# NixieClock.net
KiCad netlist of a schematic drawn in EAGLE
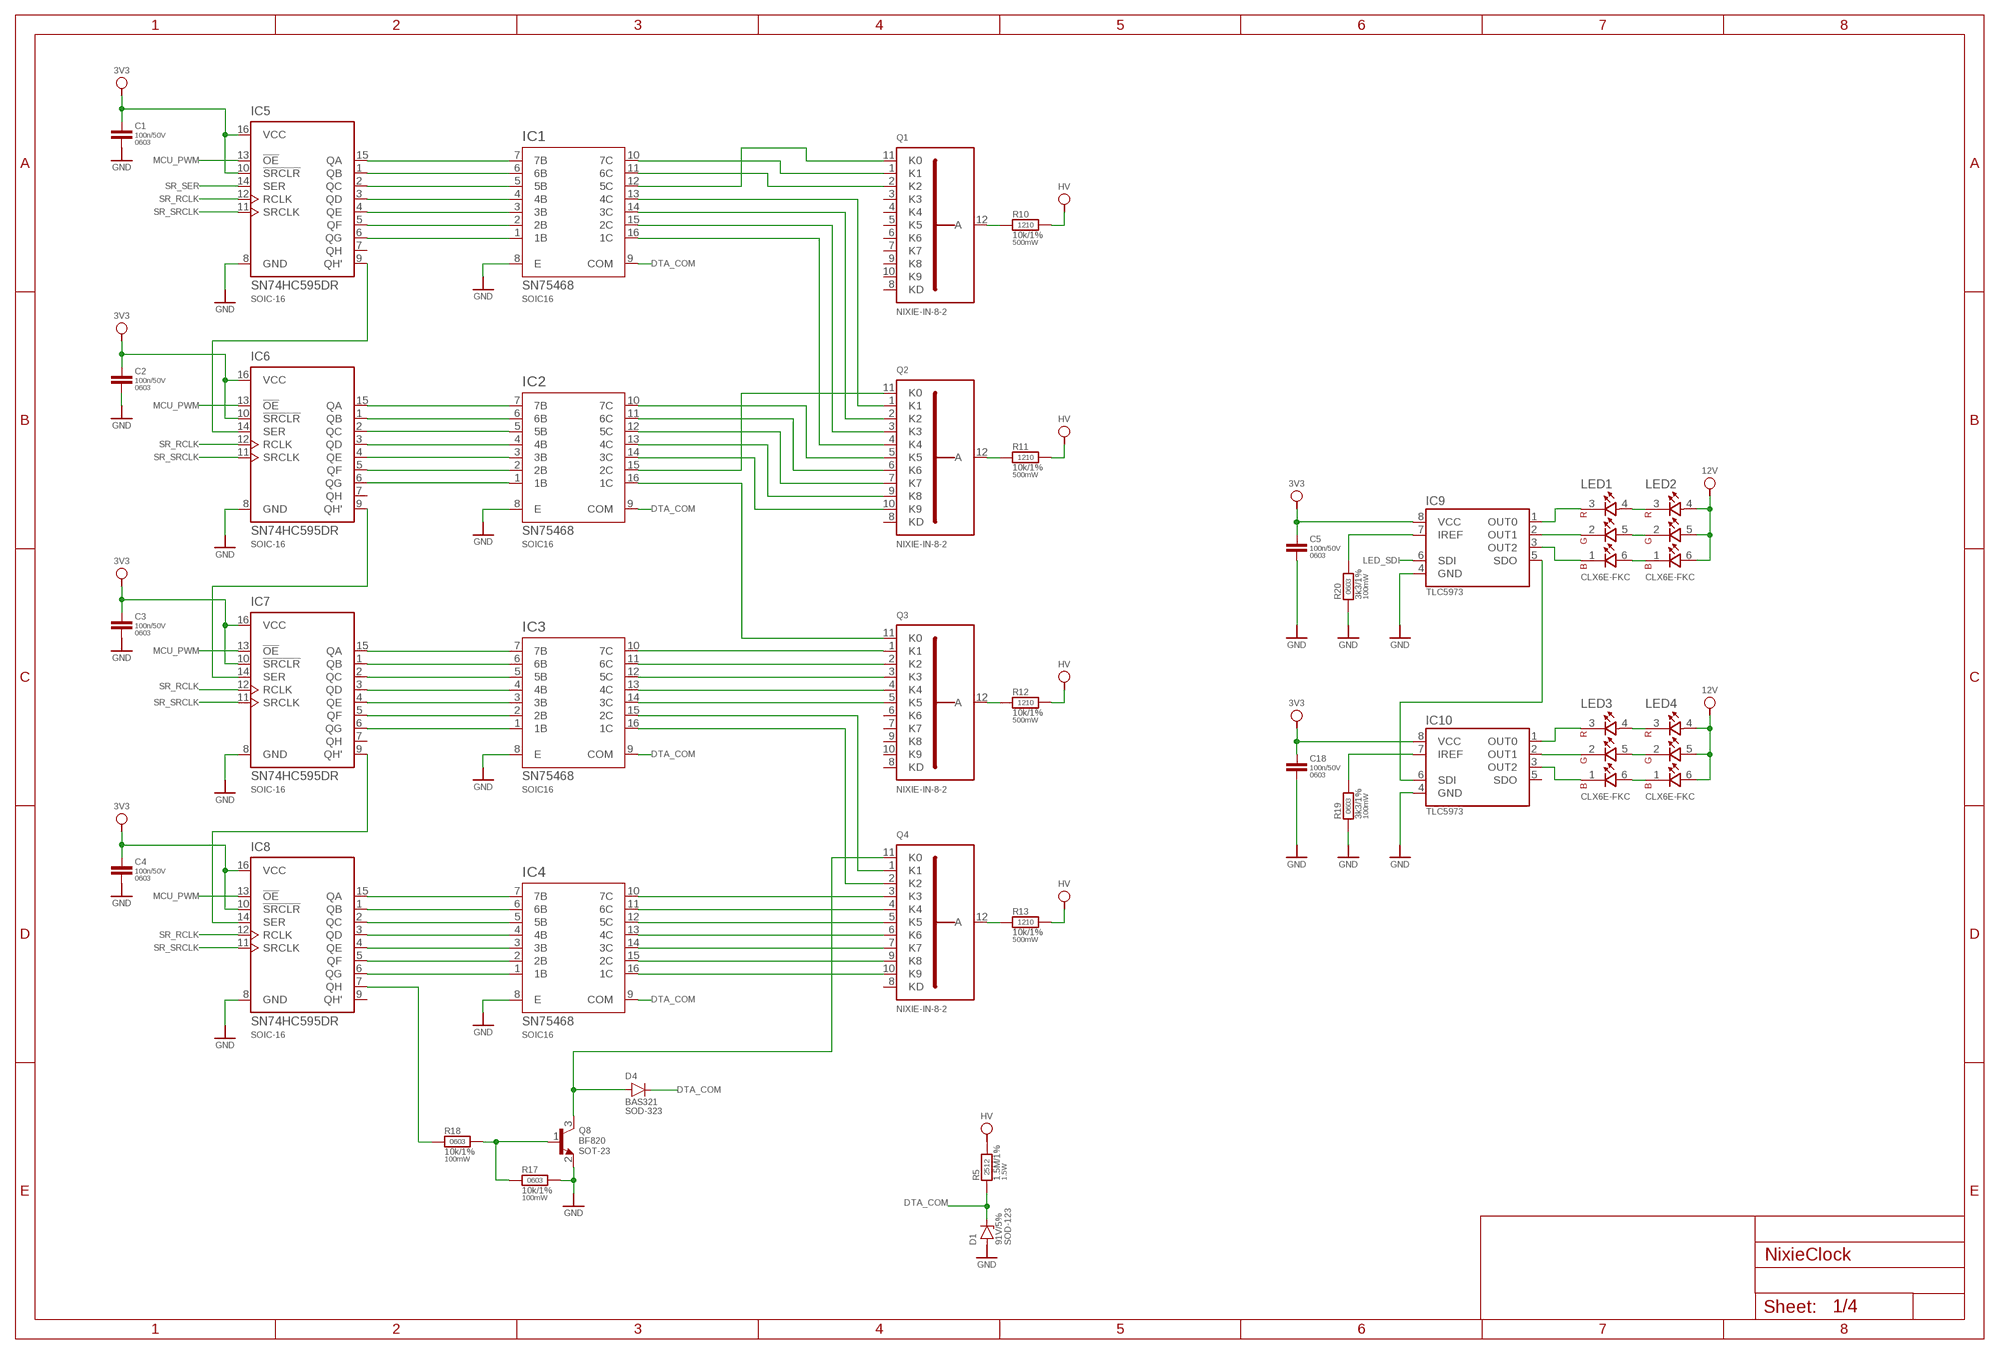
[diagram p0: schematic, sheet 1]
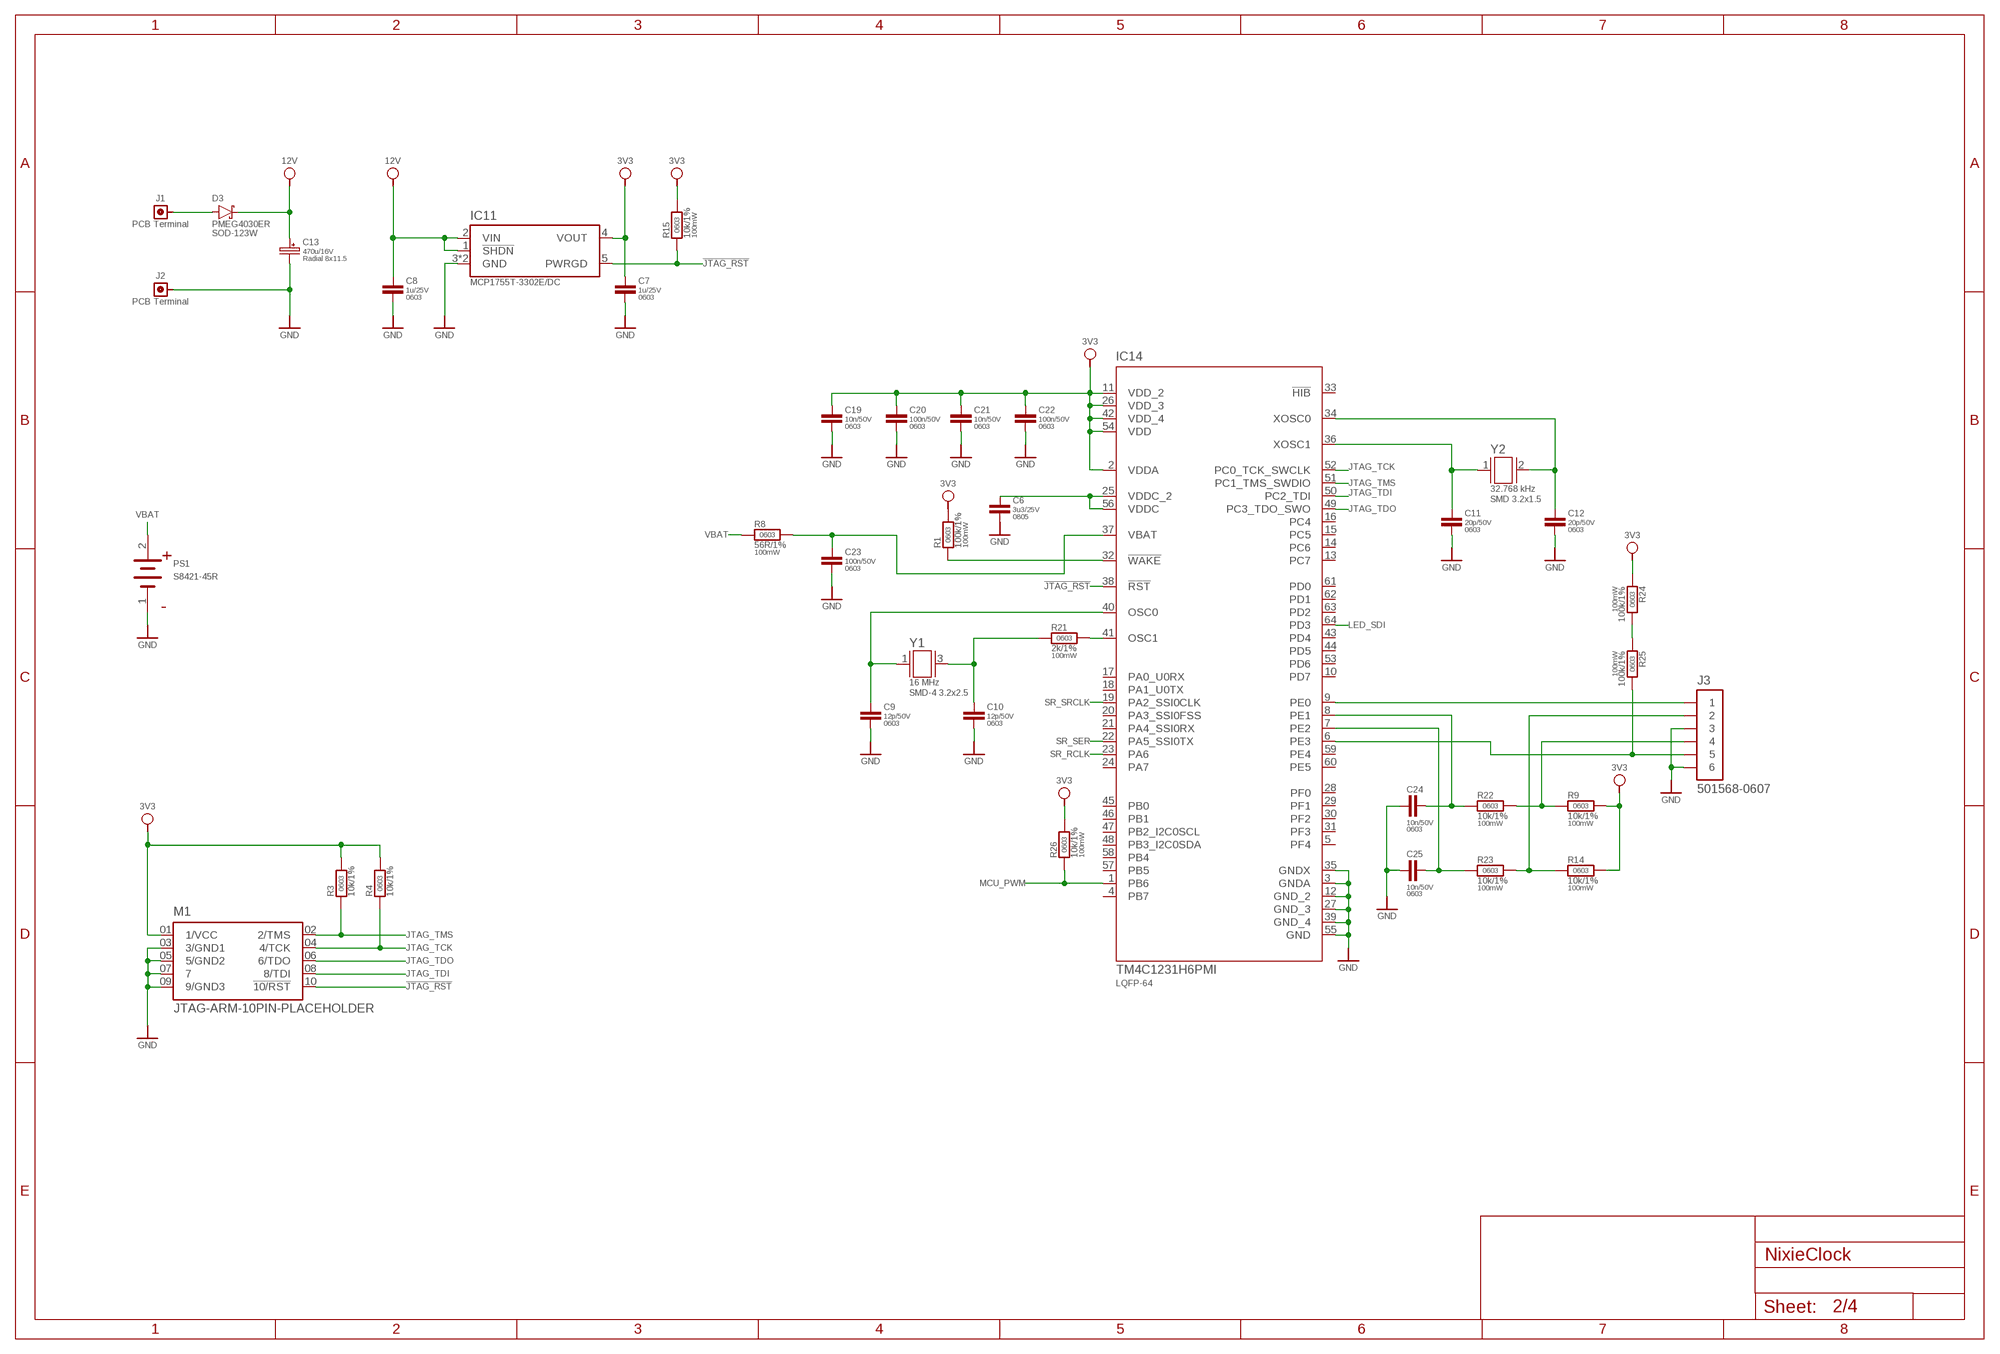
[diagram p1: schematic, sheet 2]
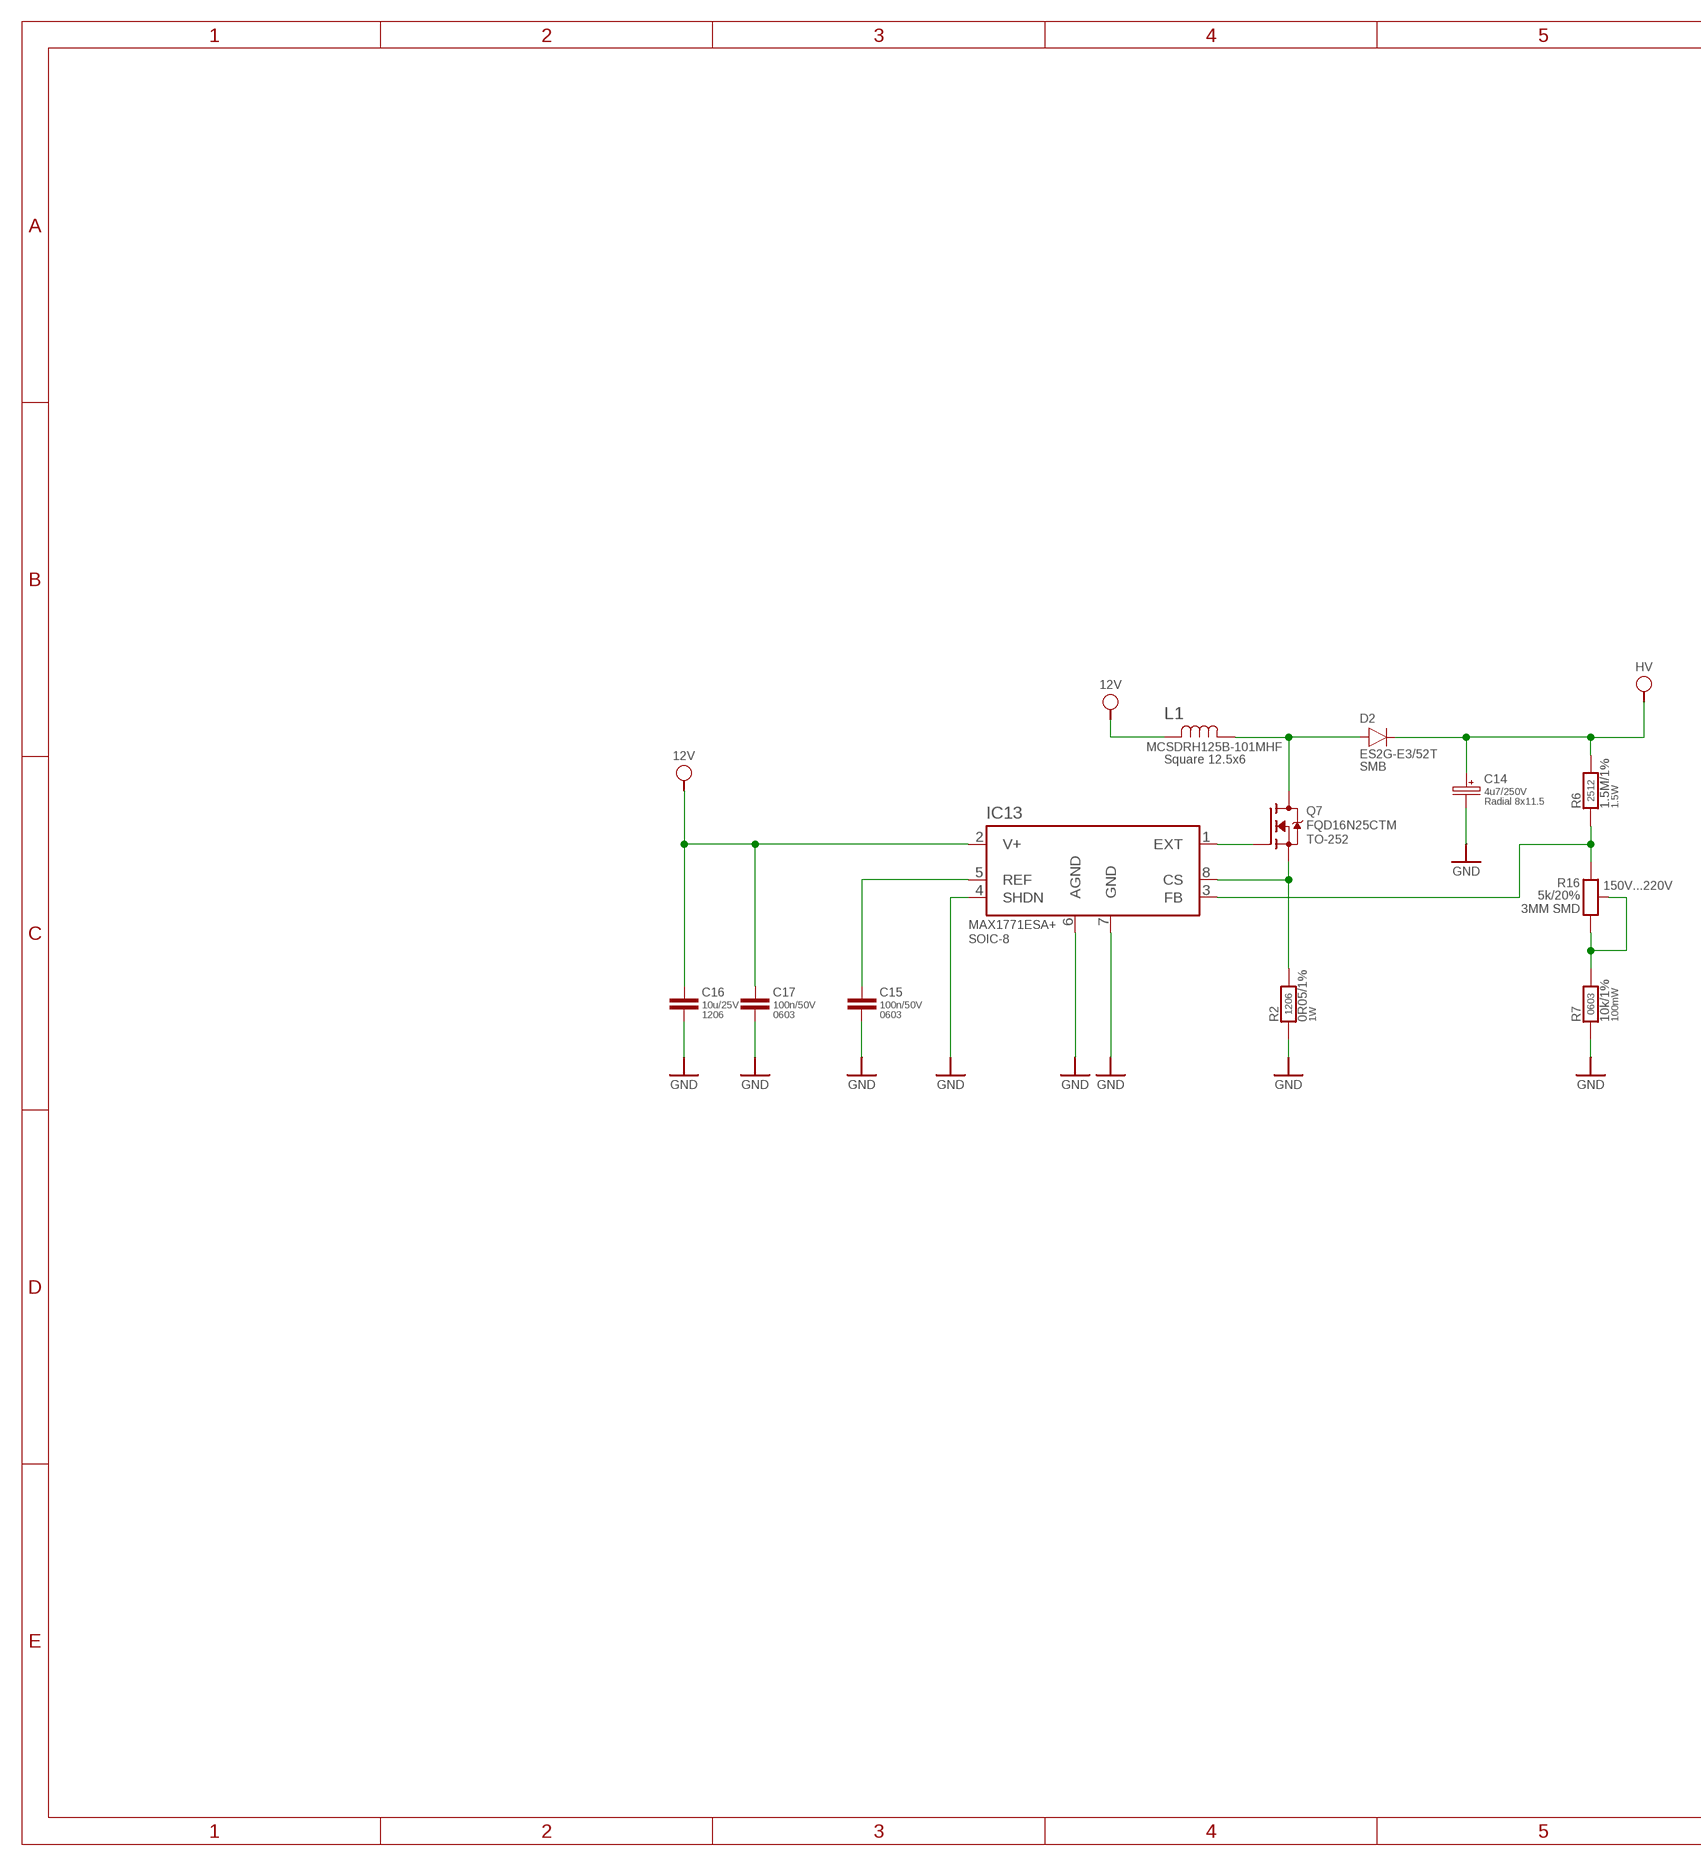
[diagram p2: schematic, sheet 3, part 1 of 2]
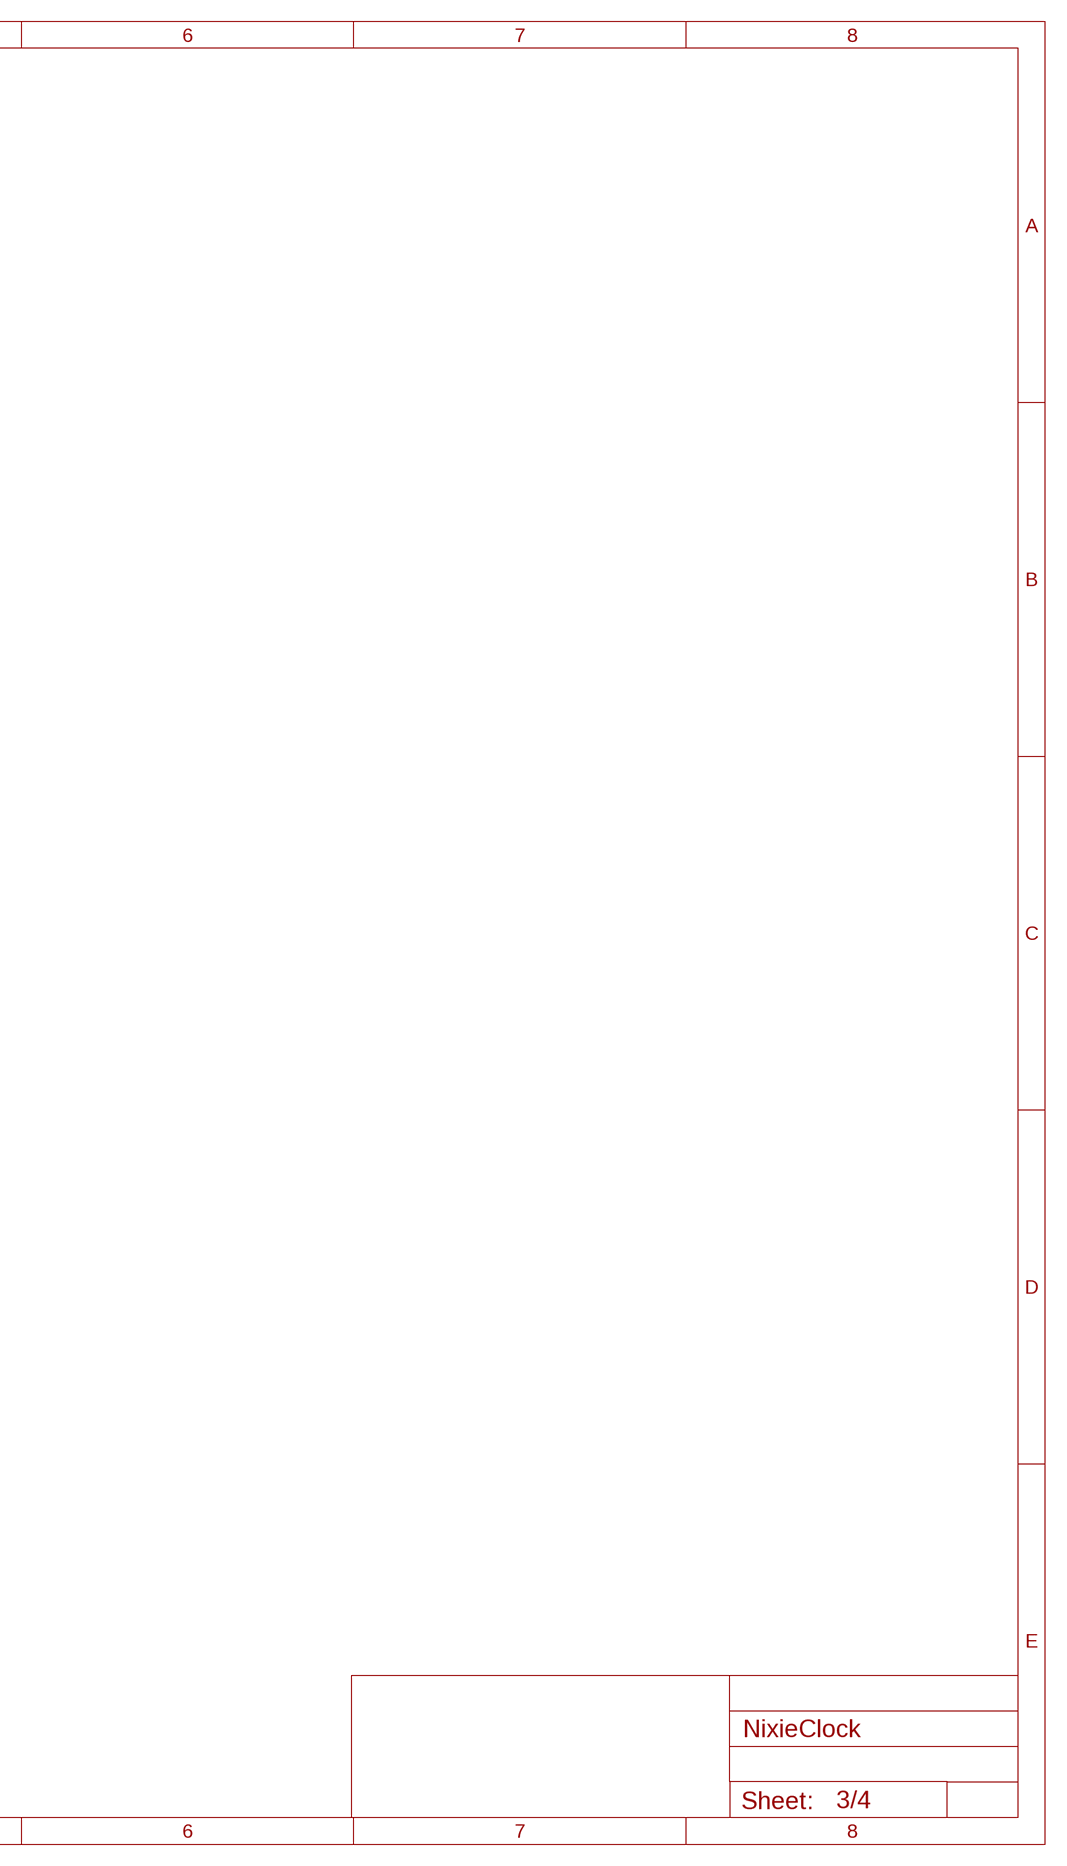
[diagram p3: schematic, sheet 3, part 2 of 2]
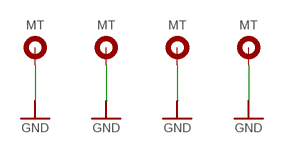
[diagram p4: schematic, sheet 4]

(export (version "E")
  (design (tool "Eeschema 10.0.6"))
  (components
    (comp (ref "MT1")
      (value "MOUNTING_HOLE_3MM")
      (footprint "eagle-import:MOUNTING_HOLE_3MM")
      (libsource (lib "eagle-import") (part "MOUNTING_HOLE_3MM"))
    )
    (comp (ref "MT2")
      (value "MOUNTING_HOLE_3MM")
      (footprint "eagle-import:MOUNTING_HOLE_3MM")
      (libsource (lib "eagle-import") (part "MOUNTING_HOLE_3MM"))
    )
    (comp (ref "MT3")
      (value "MOUNTING_HOLE_3MM")
      (footprint "eagle-import:MOUNTING_HOLE_3MM")
      (libsource (lib "eagle-import") (part "MOUNTING_HOLE_3MM"))
    )
    (comp (ref "MT4")
      (value "MOUNTING_HOLE_3MM")
      (footprint "eagle-import:MOUNTING_HOLE_3MM")
      (libsource (lib "eagle-import") (part "MOUNTING_HOLE_3MM"))
    )
    (comp (ref "C14")
      (value "4u7/250V")
      (footprint "eagle-import:CAPPRD350W60D800H1150B")
      (fields
        (field (name "PACKAGE") "Radial 8x11.5")
        (field (name "MANUFACTURER") "Panasonic")
        (field (name "PARTNUMBER") "ECA2EHG4R7")
      )
      (libsource (lib "eagle-import") (part "ECA2EHG4R7"))
    )
    (comp (ref "C15")
      (value "100n/50V")
      (footprint "eagle-import:CAPC1608X80N")
      (fields
        (field (name "PACKAGE") "0603")
        (field (name "MANUFACTURER") "KEMET")
        (field (name "PARTNUMBER") "C0603C104M5RACTU")
      )
      (libsource (lib "eagle-import") (part "C0603C104M5RACTU"))
    )
    (comp (ref "C16")
      (value "10u/25V")
      (footprint "eagle-import:CAPC3216X170N")
      (fields
        (field (name "PACKAGE") "1206")
        (field (name "MANUFACTURER") "KEMET")
        (field (name "PARTNUMBER") "C1206C106K3PACTU")
      )
      (libsource (lib "eagle-import") (part "C1206C106K3PACTU"))
    )
    (comp (ref "C17")
      (value "100n/50V")
      (footprint "eagle-import:CAPC1608X80N")
      (fields
        (field (name "PACKAGE") "0603")
        (field (name "MANUFACTURER") "KEMET")
        (field (name "PARTNUMBER") "C0603C104M5RACTU")
      )
      (libsource (lib "eagle-import") (part "C0603C104M5RACTU"))
    )
    (comp (ref "D2")
      (value "ES2G-E3/52T")
      (footprint "eagle-import:DIOM5436X245N")
      (fields (field (name "PACKAGE") "SMB") (field (name "MANUFACTURER") "VISHAY"))
      (libsource (lib "eagle-import") (part "ES2G-E3/52T"))
    )
    (comp (ref "IC13")
      (value "MAX1771ESA+")
      (footprint "eagle-import:SOIC127P600X175-8N")
      (fields (field (name "PACKAGE") "SOIC-8") (field (name "MANUFACTURER") "Maxim Integrated"))
      (libsource (lib "eagle-import") (part "MAX1771ESA+"))
    )
    (comp (ref "L1")
      (value "MCSDRH125B-101MHF")
      (footprint "eagle-import:INDM120120X600N")
      (fields (field (name "PACKAGE") "Square 12.5x6") (field (name "MANUFACTURER") "Multicomp PRO"))
      (libsource (lib "eagle-import") (part "MCSDRH125B-101MHF"))
    )
    (comp (ref "Q7")
      (value "FQD16N25CTM")
      (footprint "eagle-import:TO230P990X240-3N")
      (fields (field (name "PACKAGE") "TO-252") (field (name "MANUFACTURER") "ON Semiconductor"))
      (libsource (lib "eagle-import") (part "FQD16N25CTM"))
    )
    (comp (ref "R2")
      (value "0R05/1%")
      (footprint "eagle-import:RESC3216X70N")
      (fields
        (field (name "PARAMETER") "1W")
        (field (name "PACKAGE") "1206")
        (field (name "MANUFACTURER") "Panasonic")
        (field (name "PARTNUMBER") "ERJ8CWFR050V")
      )
      (libsource (lib "eagle-import") (part "ERJ8CWFR050V"))
    )
    (comp (ref "R6")
      (value "1.5M/1%")
      (footprint "eagle-import:RESC6331X65N")
      (fields
        (field (name "PARAMETER") "1.5W")
        (field (name "PACKAGE") "2512")
        (field (name "MANUFACTURER") "MULTICOMP PRO")
        (field (name "PARTNUMBER") "MCPWR12FTEA1504")
      )
      (libsource (lib "eagle-import") (part "MCPWR12FTEA1504"))
    )
    (comp (ref "R7")
      (value "10k/1%")
      (footprint "eagle-import:RESC1608X50N")
      (fields
        (field (name "PARAMETER") "100mW")
        (field (name "PACKAGE") "0603")
        (field (name "MANUFACTURER") "VISHAY")
        (field (name "PARTNUMBER") "CRCW060310K0FKEA")
      )
      (libsource (lib "eagle-import") (part "CRCW060310K0FKEA"))
    )
    (comp (ref "R16")
      (value "5k/20%")
      (footprint "eagle-import:22A")
      (fields (field (name "PACKAGE") "3MM SMD") (field (name "MANUFACTURER") "TT ELECTRONICS / BI TECHNOL"))
      (libsource (lib "eagle-import") (part "22AR5K"))
    )
    (comp (ref "C1")
      (value "100n/50V")
      (footprint "eagle-import:CAPC1608X80N")
      (fields
        (field (name "PACKAGE") "0603")
        (field (name "MANUFACTURER") "KEMET")
        (field (name "PARTNUMBER") "C0603C104M5RACTU")
      )
      (libsource (lib "eagle-import") (part "C0603C104M5RACTU"))
    )
    (comp (ref "C2")
      (value "100n/50V")
      (footprint "eagle-import:CAPC1608X80N")
      (fields
        (field (name "PACKAGE") "0603")
        (field (name "MANUFACTURER") "KEMET")
        (field (name "PARTNUMBER") "C0603C104M5RACTU")
      )
      (libsource (lib "eagle-import") (part "C0603C104M5RACTU"))
    )
    (comp (ref "C3")
      (value "100n/50V")
      (footprint "eagle-import:CAPC1608X80N")
      (fields
        (field (name "PACKAGE") "0603")
        (field (name "MANUFACTURER") "KEMET")
        (field (name "PARTNUMBER") "C0603C104M5RACTU")
      )
      (libsource (lib "eagle-import") (part "C0603C104M5RACTU"))
    )
    (comp (ref "C4")
      (value "100n/50V")
      (footprint "eagle-import:CAPC1608X80N")
      (fields
        (field (name "PACKAGE") "0603")
        (field (name "MANUFACTURER") "KEMET")
        (field (name "PARTNUMBER") "C0603C104M5RACTU")
      )
      (libsource (lib "eagle-import") (part "C0603C104M5RACTU"))
    )
    (comp (ref "C5")
      (value "100n/50V")
      (footprint "eagle-import:CAPC1608X80N")
      (fields
        (field (name "PACKAGE") "0603")
        (field (name "MANUFACTURER") "KEMET")
        (field (name "PARTNUMBER") "C0603C104M5RACTU")
      )
      (libsource (lib "eagle-import") (part "C0603C104M5RACTU"))
    )
    (comp (ref "C18")
      (value "100n/50V")
      (footprint "eagle-import:CAPC1608X80N")
      (fields
        (field (name "PACKAGE") "0603")
        (field (name "MANUFACTURER") "KEMET")
        (field (name "PARTNUMBER") "C0603C104M5RACTU")
      )
      (libsource (lib "eagle-import") (part "C0603C104M5RACTU"))
    )
    (comp (ref "D1")
      (value "91V/5%")
      (footprint "eagle-import:SOD3716X135N")
      (fields
        (field (name "PACKAGE") "SOD-123")
        (field (name "MANUFACTURER") "ON Semiconductor")
        (field (name "PARTNUMBER") "MMSZ5270BT1G")
      )
      (libsource (lib "eagle-import") (part "MMSZ5270BT1G"))
    )
    (comp (ref "D4")
      (value "BAS321")
      (footprint "eagle-import:SOD2512X110N")
      (fields
        (field (name "PACKAGE") "SOD-323")
        (field (name "MANUFACTURER") "NEXPERIA")
        (field (name "PARTNUMBER") "BAS321/8F")
      )
      (libsource (lib "eagle-import") (part "BAS321"))
    )
    (comp (ref "IC1")
      (value "SN75468")
      (footprint "eagle-import:SOIC127P600X175-16N")
      (fields
        (field (name "PACKAGE") "SOIC16")
        (field (name "MANUFACTURER") "Texas Instruments")
        (field (name "PARTNUMBER") "SN75468D")
      )
      (libsource (lib "eagle-import") (part "SN75468"))
    )
    (comp (ref "IC2")
      (value "SN75468")
      (footprint "eagle-import:SOIC127P600X175-16N")
      (fields
        (field (name "PACKAGE") "SOIC16")
        (field (name "MANUFACTURER") "Texas Instruments")
        (field (name "PARTNUMBER") "SN75468D")
      )
      (libsource (lib "eagle-import") (part "SN75468"))
    )
    (comp (ref "IC3")
      (value "SN75468")
      (footprint "eagle-import:SOIC127P600X175-16N")
      (fields
        (field (name "PACKAGE") "SOIC16")
        (field (name "MANUFACTURER") "Texas Instruments")
        (field (name "PARTNUMBER") "SN75468D")
      )
      (libsource (lib "eagle-import") (part "SN75468"))
    )
    (comp (ref "IC4")
      (value "SN75468")
      (footprint "eagle-import:SOIC127P600X175-16N")
      (fields
        (field (name "PACKAGE") "SOIC16")
        (field (name "MANUFACTURER") "Texas Instruments")
        (field (name "PARTNUMBER") "SN75468D")
      )
      (libsource (lib "eagle-import") (part "SN75468"))
    )
    (comp (ref "IC5")
      (value "SN74HC595DR")
      (footprint "eagle-import:SOIC127P600X175-16N")
      (fields (field (name "PACKAGE") "SOIC-16") (field (name "MANUFACTURER") "Texas Instruments"))
      (libsource (lib "eagle-import") (part "SN74HC595DR"))
    )
    (comp (ref "IC6")
      (value "SN74HC595DR")
      (footprint "eagle-import:SOIC127P600X175-16N")
      (fields (field (name "PACKAGE") "SOIC-16") (field (name "MANUFACTURER") "Texas Instruments"))
      (libsource (lib "eagle-import") (part "SN74HC595DR"))
    )
    (comp (ref "IC7")
      (value "SN74HC595DR")
      (footprint "eagle-import:SOIC127P600X175-16N")
      (fields (field (name "PACKAGE") "SOIC-16") (field (name "MANUFACTURER") "Texas Instruments"))
      (libsource (lib "eagle-import") (part "SN74HC595DR"))
    )
    (comp (ref "IC8")
      (value "SN74HC595DR")
      (footprint "eagle-import:SOIC127P600X175-16N")
      (fields (field (name "PACKAGE") "SOIC-16") (field (name "MANUFACTURER") "Texas Instruments"))
      (libsource (lib "eagle-import") (part "SN74HC595DR"))
    )
    (comp (ref "IC9")
      (value "TLC5973")
      (footprint "eagle-import:SOIC127P600X175-8N")
      (fields (field (name "MANUFACTURER") "Texas Instruments"))
      (libsource (lib "eagle-import") (part "TLC5973"))
    )
    (comp (ref "IC10")
      (value "TLC5973")
      (footprint "eagle-import:SOIC127P600X175-8N")
      (fields (field (name "MANUFACTURER") "Texas Instruments"))
      (libsource (lib "eagle-import") (part "TLC5973"))
    )
    (comp (ref "LED1")
      (value "CLX6E-FKC")
      (footprint "eagle-import:CLX6E-FKC")
      (fields (field (name "MANUFACTURER") "CREE") (field (name "PARTNUMBER") "CLX6E-FKC-CH1M1D1BB7C3D3"))
      (libsource (lib "eagle-import") (part "CLX6E-FKC"))
    )
    (comp (ref "LED2")
      (value "CLX6E-FKC")
      (footprint "eagle-import:CLX6E-FKC")
      (fields (field (name "MANUFACTURER") "CREE") (field (name "PARTNUMBER") "CLX6E-FKC-CH1M1D1BB7C3D3"))
      (libsource (lib "eagle-import") (part "CLX6E-FKC"))
    )
    (comp (ref "LED3")
      (value "CLX6E-FKC")
      (footprint "eagle-import:CLX6E-FKC")
      (fields (field (name "MANUFACTURER") "CREE") (field (name "PARTNUMBER") "CLX6E-FKC-CH1M1D1BB7C3D3"))
      (libsource (lib "eagle-import") (part "CLX6E-FKC"))
    )
    (comp (ref "LED4")
      (value "CLX6E-FKC")
      (footprint "eagle-import:CLX6E-FKC")
      (fields (field (name "MANUFACTURER") "CREE") (field (name "PARTNUMBER") "CLX6E-FKC-CH1M1D1BB7C3D3"))
      (libsource (lib "eagle-import") (part "CLX6E-FKC"))
    )
    (comp (ref "Q1")
      (value "NIXIE-IN-8-2")
      (footprint "eagle-import:NIXIE-IN-8-2")
      (libsource (lib "eagle-import") (part "NIXIE-IN-8-2"))
    )
    (comp (ref "Q2")
      (value "NIXIE-IN-8-2")
      (footprint "eagle-import:NIXIE-IN-8-2")
      (libsource (lib "eagle-import") (part "NIXIE-IN-8-2"))
    )
    (comp (ref "Q3")
      (value "NIXIE-IN-8-2")
      (footprint "eagle-import:NIXIE-IN-8-2")
      (libsource (lib "eagle-import") (part "NIXIE-IN-8-2"))
    )
    (comp (ref "Q4")
      (value "NIXIE-IN-8-2")
      (footprint "eagle-import:NIXIE-IN-8-2")
      (libsource (lib "eagle-import") (part "NIXIE-IN-8-2"))
    )
    (comp (ref "Q8")
      (value "BF820")
      (footprint "eagle-import:SOT95P230X110-3N")
      (fields (field (name "PACKAGE") "SOT-23") (field (name "MANUFACTURER") "NEXPERIA"))
      (libsource (lib "eagle-import") (part "BF820"))
    )
    (comp (ref "R5")
      (value "1.5M/1%")
      (footprint "eagle-import:RESC6331X65N")
      (fields
        (field (name "PARAMETER") "1.5W")
        (field (name "PACKAGE") "2512")
        (field (name "MANUFACTURER") "MULTICOMP PRO")
        (field (name "PARTNUMBER") "MCPWR12FTEA1504")
      )
      (libsource (lib "eagle-import") (part "MCPWR12FTEA1504"))
    )
    (comp (ref "R10")
      (value "10k/1%")
      (footprint "eagle-import:RESC3225X60N")
      (fields
        (field (name "PARAMETER") "500mW")
        (field (name "PACKAGE") "1210")
        (field (name "MANUFACTURER") "VISHAY")
        (field (name "PARTNUMBER") "CRCW121010K0FKEA")
      )
      (libsource (lib "eagle-import") (part "CRCW121010K0FKEA"))
    )
    (comp (ref "R11")
      (value "10k/1%")
      (footprint "eagle-import:RESC3225X60N")
      (fields
        (field (name "PARAMETER") "500mW")
        (field (name "PACKAGE") "1210")
        (field (name "MANUFACTURER") "VISHAY")
        (field (name "PARTNUMBER") "CRCW121010K0FKEA")
      )
      (libsource (lib "eagle-import") (part "CRCW121010K0FKEA"))
    )
    (comp (ref "R12")
      (value "10k/1%")
      (footprint "eagle-import:RESC3225X60N")
      (fields
        (field (name "PARAMETER") "500mW")
        (field (name "PACKAGE") "1210")
        (field (name "MANUFACTURER") "VISHAY")
        (field (name "PARTNUMBER") "CRCW121010K0FKEA")
      )
      (libsource (lib "eagle-import") (part "CRCW121010K0FKEA"))
    )
    (comp (ref "R13")
      (value "10k/1%")
      (footprint "eagle-import:RESC3225X60N")
      (fields
        (field (name "PARAMETER") "500mW")
        (field (name "PACKAGE") "1210")
        (field (name "MANUFACTURER") "VISHAY")
        (field (name "PARTNUMBER") "CRCW121010K0FKEA")
      )
      (libsource (lib "eagle-import") (part "CRCW121010K0FKEA"))
    )
    (comp (ref "R17")
      (value "10k/1%")
      (footprint "eagle-import:RESC1608X50N")
      (fields
        (field (name "PARAMETER") "100mW")
        (field (name "PACKAGE") "0603")
        (field (name "MANUFACTURER") "VISHAY")
        (field (name "PARTNUMBER") "CRCW060310K0FKEA")
      )
      (libsource (lib "eagle-import") (part "CRCW060310K0FKEA"))
    )
    (comp (ref "R18")
      (value "10k/1%")
      (footprint "eagle-import:RESC1608X50N")
      (fields
        (field (name "PARAMETER") "100mW")
        (field (name "PACKAGE") "0603")
        (field (name "MANUFACTURER") "VISHAY")
        (field (name "PARTNUMBER") "CRCW060310K0FKEA")
      )
      (libsource (lib "eagle-import") (part "CRCW060310K0FKEA"))
    )
    (comp (ref "R19")
      (value "3k3/1%")
      (footprint "eagle-import:RESC1608X50N")
      (fields
        (field (name "PARAMETER") "100mW")
        (field (name "PACKAGE") "0603")
        (field (name "MANUFACTURER") "MULTICOMP PRO")
        (field (name "PARTNUMBER") "MCWR06X3301FTL")
      )
      (libsource (lib "eagle-import") (part "MCWR06X3301FTL"))
    )
    (comp (ref "R20")
      (value "3k3/1%")
      (footprint "eagle-import:RESC1608X50N")
      (fields
        (field (name "PARAMETER") "100mW")
        (field (name "PACKAGE") "0603")
        (field (name "MANUFACTURER") "MULTICOMP PRO")
        (field (name "PARTNUMBER") "MCWR06X3301FTL")
      )
      (libsource (lib "eagle-import") (part "MCWR06X3301FTL"))
    )
    (comp (ref "C6")
      (value "3u3/25V")
      (footprint "eagle-import:CAPC2012X145N")
      (fields
        (field (name "PACKAGE") "0805")
        (field (name "MANUFACTURER") "TDK")
        (field (name "PARTNUMBER") "C2012X7R1E335K125AB")
      )
      (libsource (lib "eagle-import") (part "C2012X7R1E335K125"))
    )
    (comp (ref "C7")
      (value "1u/25V")
      (footprint "eagle-import:CAPC1608X80N")
      (fields
        (field (name "PACKAGE") "0603")
        (field (name "MANUFACTURER") "SAMSUNG ELECTRO-MECHANICS")
        (field (name "PARTNUMBER") "CL10A105KA8NNNC")
      )
      (libsource (lib "eagle-import") (part "CL10A105KA8NNNC"))
    )
    (comp (ref "C8")
      (value "1u/25V")
      (footprint "eagle-import:CAPC1608X80N")
      (fields
        (field (name "PACKAGE") "0603")
        (field (name "MANUFACTURER") "SAMSUNG ELECTRO-MECHANICS")
        (field (name "PARTNUMBER") "CL10A105KA8NNNC")
      )
      (libsource (lib "eagle-import") (part "CL10A105KA8NNNC"))
    )
    (comp (ref "C9")
      (value "12p/50V")
      (footprint "eagle-import:CAPC1608X80N")
      (fields
        (field (name "PACKAGE") "0603")
        (field (name "MANUFACTURER") "KEMET")
        (field (name "PARTNUMBER") "C0603C120J5GACTU")
      )
      (libsource (lib "eagle-import") (part "C0603C120J5GACTU"))
    )
    (comp (ref "C10")
      (value "12p/50V")
      (footprint "eagle-import:CAPC1608X80N")
      (fields
        (field (name "PACKAGE") "0603")
        (field (name "MANUFACTURER") "KEMET")
        (field (name "PARTNUMBER") "C0603C120J5GACTU")
      )
      (libsource (lib "eagle-import") (part "C0603C120J5GACTU"))
    )
    (comp (ref "C11")
      (value "20p/50V")
      (footprint "eagle-import:CAPC1608X80N")
      (fields
        (field (name "PACKAGE") "0603")
        (field (name "MANUFACTURER") "KEMET")
        (field (name "PARTNUMBER") "C0603C200J1GACTU")
      )
      (libsource (lib "eagle-import") (part "C0603C200J1GACTU"))
    )
    (comp (ref "C12")
      (value "20p/50V")
      (footprint "eagle-import:CAPC1608X80N")
      (fields
        (field (name "PACKAGE") "0603")
        (field (name "MANUFACTURER") "KEMET")
        (field (name "PARTNUMBER") "C0603C200J1GACTU")
      )
      (libsource (lib "eagle-import") (part "C0603C200J1GACTU"))
    )
    (comp (ref "C13")
      (value "470u/16V")
      (footprint "eagle-import:CAPPRD350W60D800H1150B")
      (fields
        (field (name "PACKAGE") "Radial 8x11.5")
        (field (name "MANUFACTURER") "Panasonic")
        (field (name "PARTNUMBER") "ECA1CM471")
      )
      (libsource (lib "eagle-import") (part "ECA1CM471"))
    )
    (comp (ref "C19")
      (value "10n/50V")
      (footprint "eagle-import:CAPC1608X80N")
      (fields
        (field (name "PACKAGE") "0603")
        (field (name "MANUFACTURER") "KEMET")
        (field (name "PARTNUMBER") "C0603C103K5RACTU")
      )
      (libsource (lib "eagle-import") (part "C0603C103K5RACTU"))
    )
    (comp (ref "C20")
      (value "100n/50V")
      (footprint "eagle-import:CAPC1608X80N")
      (fields
        (field (name "PACKAGE") "0603")
        (field (name "MANUFACTURER") "KEMET")
        (field (name "PARTNUMBER") "C0603C104M5RACTU")
      )
      (libsource (lib "eagle-import") (part "C0603C104M5RACTU"))
    )
    (comp (ref "C21")
      (value "10n/50V")
      (footprint "eagle-import:CAPC1608X80N")
      (fields
        (field (name "PACKAGE") "0603")
        (field (name "MANUFACTURER") "KEMET")
        (field (name "PARTNUMBER") "C0603C103K5RACTU")
      )
      (libsource (lib "eagle-import") (part "C0603C103K5RACTU"))
    )
    (comp (ref "C22")
      (value "100n/50V")
      (footprint "eagle-import:CAPC1608X80N")
      (fields
        (field (name "PACKAGE") "0603")
        (field (name "MANUFACTURER") "KEMET")
        (field (name "PARTNUMBER") "C0603C104M5RACTU")
      )
      (libsource (lib "eagle-import") (part "C0603C104M5RACTU"))
    )
    (comp (ref "C23")
      (value "100n/50V")
      (footprint "eagle-import:CAPC1608X80N")
      (fields
        (field (name "PACKAGE") "0603")
        (field (name "MANUFACTURER") "KEMET")
        (field (name "PARTNUMBER") "C0603C104M5RACTU")
      )
      (libsource (lib "eagle-import") (part "C0603C104M5RACTU"))
    )
    (comp (ref "C24")
      (value "10n/50V")
      (footprint "eagle-import:CAPC1608X80N")
      (fields
        (field (name "PACKAGE") "0603")
        (field (name "MANUFACTURER") "KEMET")
        (field (name "PARTNUMBER") "C0603C103K5RACTU")
      )
      (libsource (lib "eagle-import") (part "C0603C103K5RACTU"))
    )
    (comp (ref "C25")
      (value "10n/50V")
      (footprint "eagle-import:CAPC1608X80N")
      (fields
        (field (name "PACKAGE") "0603")
        (field (name "MANUFACTURER") "KEMET")
        (field (name "PARTNUMBER") "C0603C103K5RACTU")
      )
      (libsource (lib "eagle-import") (part "C0603C103K5RACTU"))
    )
    (comp (ref "D3")
      (value "PMEG4030ER")
      (footprint "eagle-import:SODFL3517X110N")
      (fields
        (field (name "PACKAGE") "SOD-123W")
        (field (name "MANUFACTURER") "NEXPERIA")
        (field (name "PARTNUMBER") "PMEG4030ER,115")
      )
      (libsource (lib "eagle-import") (part "PMEG4010CEJ"))
    )
    (comp (ref "IC11")
      (value "MCP1755T-3302E/DC")
      (footprint "eagle-import:SOT127P700X180-6N")
      (fields (field (name "MANUFACTURER") "MICROCHIP"))
      (libsource (lib "eagle-import") (part "MCP1755T-3302E/DC"))
    )
    (comp (ref "IC14")
      (value "TM4C1231H6PMI")
      (footprint "eagle-import:QFP50P1200X1200X160-64N")
      (fields (field (name "PACKAGE") "LQFP-64") (field (name "MANUFACTURER") "Texas Instruments"))
      (libsource (lib "eagle-import") (part "TM4C1231H6PMI"))
    )
    (comp (ref "J1")
      (value "PCB Terminal")
      (footprint "eagle-import:PCB_TERMINAL_PAD")
      (libsource (lib "eagle-import") (part "PCB_TERMINAL_PAD"))
    )
    (comp (ref "J2")
      (value "PCB Terminal")
      (footprint "eagle-import:PCB_TERMINAL_PAD")
      (libsource (lib "eagle-import") (part "PCB_TERMINAL_PAD"))
    )
    (comp (ref "J3")
      (value "501568-0607")
      (footprint "eagle-import:MOLEX_501568-0607")
      (fields (field (name "MANUFACTURER") "MOLEX"))
      (libsource (lib "eagle-import") (part "MOLEX_501568-0607"))
    )
    (comp (ref "M1")
      (value "JTAG-ARM-10PIN-PLACEHOLDER")
      (footprint "eagle-import:JTAG-ARM-10PIN-PLACEHOLDER")
      (libsource (lib "eagle-import") (part "JTAG-ARM-10PIN-PLACEHOLDER"))
    )
    (comp (ref "PS1")
      (value "S8421-45R")
      (footprint "eagle-import:S8421-45R")
      (fields (field (name "MANUFACTURER") "Harwin"))
      (libsource (lib "eagle-import") (part "S8421-45R"))
    )
    (comp (ref "R1")
      (value "100k/1%")
      (footprint "eagle-import:RESC1608X50N")
      (fields
        (field (name "PARAMETER") "100mW")
        (field (name "PACKAGE") "0603")
        (field (name "MANUFACTURER") "VISHAY")
        (field (name "PARTNUMBER") "CRCW0603100KFKEA")
      )
      (libsource (lib "eagle-import") (part "CRCW0603100KFKEA"))
    )
    (comp (ref "R3")
      (value "10k/1%")
      (footprint "eagle-import:RESC1608X50N")
      (fields
        (field (name "PACKAGE") "0603")
        (field (name "MANUFACTURER") "VISHAY")
        (field (name "PARTNUMBER") "CRCW060310K0FKEA")
      )
      (libsource (lib "eagle-import") (part "CRCW060310K0FKEA"))
    )
    (comp (ref "R4")
      (value "10k/1%")
      (footprint "eagle-import:RESC1608X50N")
      (fields
        (field (name "PACKAGE") "0603")
        (field (name "MANUFACTURER") "VISHAY")
        (field (name "PARTNUMBER") "CRCW060310K0FKEA")
      )
      (libsource (lib "eagle-import") (part "CRCW060310K0FKEA"))
    )
    (comp (ref "R8")
      (value "56R/1%")
      (footprint "eagle-import:RESC1608X50N")
      (fields
        (field (name "PARAMETER") "100mW")
        (field (name "PACKAGE") "0603")
        (field (name "MANUFACTURER") "VISHAY")
        (field (name "PARTNUMBER") "CRCW060333R0FKEA")
      )
      (libsource (lib "eagle-import") (part "CRCW060356R0FKEA"))
    )
    (comp (ref "R9")
      (value "10k/1%")
      (footprint "eagle-import:RESC1608X50N")
      (fields
        (field (name "PARAMETER") "100mW")
        (field (name "PACKAGE") "0603")
        (field (name "MANUFACTURER") "VISHAY")
        (field (name "PARTNUMBER") "CRCW060310K0FKEA")
      )
      (libsource (lib "eagle-import") (part "CRCW060310K0FKEA"))
    )
    (comp (ref "R14")
      (value "10k/1%")
      (footprint "eagle-import:RESC1608X50N")
      (fields
        (field (name "PARAMETER") "100mW")
        (field (name "PACKAGE") "0603")
        (field (name "MANUFACTURER") "VISHAY")
        (field (name "PARTNUMBER") "CRCW060310K0FKEA")
      )
      (libsource (lib "eagle-import") (part "CRCW060310K0FKEA"))
    )
    (comp (ref "R15")
      (value "10k/1%")
      (footprint "eagle-import:RESC1608X50N")
      (fields
        (field (name "PARAMETER") "100mW")
        (field (name "PACKAGE") "0603")
        (field (name "MANUFACTURER") "VISHAY")
        (field (name "PARTNUMBER") "CRCW060310K0FKEA")
      )
      (libsource (lib "eagle-import") (part "CRCW060310K0FKEA"))
    )
    (comp (ref "R21")
      (value "2k/1%")
      (footprint "eagle-import:RESC1608X50N")
      (fields
        (field (name "PARAMETER") "100mW")
        (field (name "PACKAGE") "0603")
        (field (name "MANUFACTURER") "VISHAY")
        (field (name "PARTNUMBER") "CRCW06032K00FKEA")
      )
      (libsource (lib "eagle-import") (part "CRCW06032K00FKEA"))
    )
    (comp (ref "R22")
      (value "10k/1%")
      (footprint "eagle-import:RESC1608X50N")
      (fields
        (field (name "PARAMETER") "100mW")
        (field (name "PACKAGE") "0603")
        (field (name "MANUFACTURER") "VISHAY")
        (field (name "PARTNUMBER") "CRCW060310K0FKEA")
      )
      (libsource (lib "eagle-import") (part "CRCW060310K0FKEA"))
    )
    (comp (ref "R23")
      (value "10k/1%")
      (footprint "eagle-import:RESC1608X50N")
      (fields
        (field (name "PARAMETER") "100mW")
        (field (name "PACKAGE") "0603")
        (field (name "MANUFACTURER") "VISHAY")
        (field (name "PARTNUMBER") "CRCW060310K0FKEA")
      )
      (libsource (lib "eagle-import") (part "CRCW060310K0FKEA"))
    )
    (comp (ref "R24")
      (value "100k/1%")
      (footprint "eagle-import:RESC1608X50N")
      (fields
        (field (name "PARAMETER") "100mW")
        (field (name "PACKAGE") "0603")
        (field (name "MANUFACTURER") "VISHAY")
        (field (name "PARTNUMBER") "CRCW0603100KFKEA")
      )
      (libsource (lib "eagle-import") (part "CRCW0603100KFKEA"))
    )
    (comp (ref "R25")
      (value "100k/1%")
      (footprint "eagle-import:RESC1608X50N")
      (fields
        (field (name "PARAMETER") "100mW")
        (field (name "PACKAGE") "0603")
        (field (name "MANUFACTURER") "VISHAY")
        (field (name "PARTNUMBER") "CRCW0603100KFKEA")
      )
      (libsource (lib "eagle-import") (part "CRCW0603100KFKEA"))
    )
    (comp (ref "R26")
      (value "10k/1%")
      (footprint "eagle-import:RESC1608X50N")
      (fields
        (field (name "PARAMETER") "100mW")
        (field (name "PACKAGE") "0603")
        (field (name "MANUFACTURER") "VISHAY")
        (field (name "PARTNUMBER") "CRCW060310K0FKEA")
      )
      (libsource (lib "eagle-import") (part "CRCW060310K0FKEA"))
    )
    (comp (ref "Y1")
      (value "16 MHz")
      (footprint "eagle-import:OSCCC320X250X100N")
      (fields
        (field (name "PACKAGE") "SMD-4 3.2x2.5")
        (field (name "MANUFACTURER") "ABRACON")
        (field (name "PARTNUMBER") "MCSJK-7U-16.00-10-10-80-B-10")
      )
      (libsource (lib "eagle-import") (part "MCSJK-7U-16.00-10-10-80-B-10"))
    )
    (comp (ref "Y2")
      (value "32.768 kHz")
      (footprint "eagle-import:OSCCC320X150X90N")
      (fields
        (field (name "PACKAGE") "SMD 3.2x1.5")
        (field (name "MANUFACTURER") "ABRACON")
        (field (name "PARTNUMBER") "ABS07AIG-32.768KHZ-1-T")
      )
      (libsource (lib "eagle-import") (part "ABS07AIG-32.768KHZ-1-T"))
    )
  )
  (nets
    (net (code "1") (name "3V3") (class "Default")
      (node (ref "C1") (pin "1") (pinfunction "1_1") (pintype "passive"))
      (node (ref "C18") (pin "1") (pinfunction "1_1") (pintype "passive"))
      (node (ref "C19") (pin "1") (pinfunction "1_1") (pintype "passive"))
      (node (ref "C2") (pin "1") (pinfunction "1_1") (pintype "passive"))
      (node (ref "C20") (pin "1") (pinfunction "1_1") (pintype "passive"))
      (node (ref "C21") (pin "1") (pinfunction "1_1") (pintype "passive"))
      (node (ref "C22") (pin "1") (pinfunction "1_1") (pintype "passive"))
      (node (ref "C3") (pin "1") (pinfunction "1_1") (pintype "passive"))
      (node (ref "C4") (pin "1") (pinfunction "1_1") (pintype "passive"))
      (node (ref "C5") (pin "1") (pinfunction "1_1") (pintype "passive"))
      (node (ref "C7") (pin "1") (pinfunction "1_1") (pintype "passive"))
      (node (ref "IC10") (pin "8") (pinfunction "VCC_8") (pintype "power_in"))
      (node (ref "IC11") (pin "4") (pinfunction "VOUT_4") (pintype "bidirectional"))
      (node (ref "IC14") (pin "11") (pinfunction "VDD_2_11") (pintype "power_in"))
      (node (ref "IC14") (pin "2") (pinfunction "VDDA_2") (pintype "power_in"))
      (node (ref "IC14") (pin "26") (pinfunction "VDD_3_26") (pintype "power_in"))
      (node (ref "IC14") (pin "42") (pinfunction "VDD_4_42") (pintype "power_in"))
      (node (ref "IC14") (pin "54") (pinfunction "VDD_54") (pintype "power_in"))
      (node (ref "IC5") (pin "10") (pinfunction "~{SRCLR}_10") (pintype "input"))
      (node (ref "IC5") (pin "16") (pinfunction "VCC_16") (pintype "power_in"))
      (node (ref "IC6") (pin "10") (pinfunction "~{SRCLR}_10") (pintype "input"))
      (node (ref "IC6") (pin "16") (pinfunction "VCC_16") (pintype "power_in"))
      (node (ref "IC7") (pin "10") (pinfunction "~{SRCLR}_10") (pintype "input"))
      (node (ref "IC7") (pin "16") (pinfunction "VCC_16") (pintype "power_in"))
      (node (ref "IC8") (pin "10") (pinfunction "~{SRCLR}_10") (pintype "input"))
      (node (ref "IC8") (pin "16") (pinfunction "VCC_16") (pintype "power_in"))
      (node (ref "IC9") (pin "8") (pinfunction "VCC_8") (pintype "power_in"))
      (node (ref "M1") (pin "01") (pinfunction "1/VCC_01") (pintype "passive"))
      (node (ref "R1") (pin "2") (pinfunction "2_2") (pintype "passive"))
      (node (ref "R14") (pin "2") (pinfunction "2_2") (pintype "passive"))
      (node (ref "R15") (pin "2") (pinfunction "2_2") (pintype "passive"))
      (node (ref "R24") (pin "1") (pinfunction "1_1") (pintype "passive"))
      (node (ref "R26") (pin "2") (pinfunction "2_2") (pintype "passive"))
      (node (ref "R3") (pin "2") (pinfunction "2_2") (pintype "passive"))
      (node (ref "R4") (pin "2") (pinfunction "2_2") (pintype "passive"))
      (node (ref "R9") (pin "2") (pinfunction "2_2") (pintype "passive"))
    )
    (net (code "2") (name "12V") (class "Default")
      (node (ref "C13") (pin "1") (pinfunction "1_1") (pintype "passive"))
      (node (ref "C16") (pin "1") (pinfunction "1_1") (pintype "passive"))
      (node (ref "C17") (pin "1") (pinfunction "1_1") (pintype "passive"))
      (node (ref "C8") (pin "1") (pinfunction "1_1") (pintype "passive"))
      (node (ref "D3") (pin "1") (pinfunction "1_1") (pintype "passive"))
      (node (ref "IC11") (pin "1") (pinfunction "~{SHDN}_1") (pintype "bidirectional"))
      (node (ref "IC11") (pin "2") (pinfunction "VIN_2") (pintype "bidirectional"))
      (node (ref "IC13") (pin "2") (pinfunction "V+_2") (pintype "power_in"))
      (node (ref "L1") (pin "1") (pinfunction "1_1") (pintype "passive"))
      (node (ref "LED2") (pin "4") (pinfunction "ARED_4") (pintype "passive"))
      (node (ref "LED2") (pin "5") (pinfunction "AGREEN_5") (pintype "passive"))
      (node (ref "LED2") (pin "6") (pinfunction "ABLUE_6") (pintype "passive"))
      (node (ref "LED4") (pin "4") (pinfunction "ARED_4") (pintype "passive"))
      (node (ref "LED4") (pin "5") (pinfunction "AGREEN_5") (pintype "passive"))
      (node (ref "LED4") (pin "6") (pinfunction "ABLUE_6") (pintype "passive"))
    )
    (net (code "3") (name "DTA_COM") (class "Default")
      (node (ref "D1") (pin "1") (pinfunction "1_1") (pintype "passive"))
      (node (ref "D4") (pin "1") (pinfunction "1_1") (pintype "passive"))
      (node (ref "IC1") (pin "9") (pinfunction "COM_9") (pintype "bidirectional"))
      (node (ref "IC2") (pin "9") (pinfunction "COM_9") (pintype "bidirectional"))
      (node (ref "IC3") (pin "9") (pinfunction "COM_9") (pintype "bidirectional"))
      (node (ref "IC4") (pin "9") (pinfunction "COM_9") (pintype "bidirectional"))
      (node (ref "R5") (pin "1") (pinfunction "1_1") (pintype "passive"))
    )
    (net (code "4") (name "GND") (class "Default")
      (node (ref "C1") (pin "2") (pinfunction "2_2") (pintype "passive"))
      (node (ref "C10") (pin "2") (pinfunction "2_2") (pintype "passive"))
      (node (ref "C11") (pin "2") (pinfunction "2_2") (pintype "passive"))
      (node (ref "C12") (pin "2") (pinfunction "2_2") (pintype "passive"))
      (node (ref "C13") (pin "2") (pinfunction "2_2") (pintype "passive"))
      (node (ref "C14") (pin "2") (pinfunction "2_2") (pintype "passive"))
      (node (ref "C15") (pin "2") (pinfunction "2_2") (pintype "passive"))
      (node (ref "C16") (pin "2") (pinfunction "2_2") (pintype "passive"))
      (node (ref "C17") (pin "2") (pinfunction "2_2") (pintype "passive"))
      (node (ref "C18") (pin "2") (pinfunction "2_2") (pintype "passive"))
      (node (ref "C19") (pin "2") (pinfunction "2_2") (pintype "passive"))
      (node (ref "C2") (pin "2") (pinfunction "2_2") (pintype "passive"))
      (node (ref "C20") (pin "2") (pinfunction "2_2") (pintype "passive"))
      (node (ref "C21") (pin "2") (pinfunction "2_2") (pintype "passive"))
      (node (ref "C22") (pin "2") (pinfunction "2_2") (pintype "passive"))
      (node (ref "C23") (pin "2") (pinfunction "2_2") (pintype "passive"))
      (node (ref "C24") (pin "1") (pinfunction "1_1") (pintype "passive"))
      (node (ref "C25") (pin "1") (pinfunction "1_1") (pintype "passive"))
      (node (ref "C3") (pin "2") (pinfunction "2_2") (pintype "passive"))
      (node (ref "C4") (pin "2") (pinfunction "2_2") (pintype "passive"))
      (node (ref "C5") (pin "2") (pinfunction "2_2") (pintype "passive"))
      (node (ref "C6") (pin "2") (pinfunction "2_2") (pintype "passive"))
      (node (ref "C7") (pin "2") (pinfunction "2_2") (pintype "passive"))
      (node (ref "C8") (pin "2") (pinfunction "2_2") (pintype "passive"))
      (node (ref "C9") (pin "2") (pinfunction "2_2") (pintype "passive"))
      (node (ref "D1") (pin "2") (pinfunction "2_2") (pintype "passive"))
      (node (ref "IC1") (pin "8") (pinfunction "E_8") (pintype "power_in"))
      (node (ref "IC10") (pin "4") (pinfunction "GND_4") (pintype "power_in"))
      (node (ref "IC11") (pin "3") (pinfunction "GND_3") (pintype "bidirectional"))
      (node (ref "IC11") (pin "6") (pinfunction "GND_6") (pintype "bidirectional"))
      (node (ref "IC13") (pin "4") (pinfunction "SHDN_4") (pintype "input"))
      (node (ref "IC13") (pin "6") (pinfunction "AGND_6") (pintype "power_in"))
      (node (ref "IC13") (pin "7") (pinfunction "GND_7") (pintype "power_in"))
      (node (ref "IC14") (pin "12") (pinfunction "GND_2_12") (pintype "power_in"))
      (node (ref "IC14") (pin "27") (pinfunction "GND_3_27") (pintype "power_in"))
      (node (ref "IC14") (pin "3") (pinfunction "GNDA_3") (pintype "power_in"))
      (node (ref "IC14") (pin "35") (pinfunction "GNDX_35") (pintype "power_in"))
      (node (ref "IC14") (pin "39") (pinfunction "GND_4_39") (pintype "power_in"))
      (node (ref "IC14") (pin "55") (pinfunction "GND_55") (pintype "power_in"))
      (node (ref "IC2") (pin "8") (pinfunction "E_8") (pintype "power_in"))
      (node (ref "IC3") (pin "8") (pinfunction "E_8") (pintype "power_in"))
      (node (ref "IC4") (pin "8") (pinfunction "E_8") (pintype "power_in"))
      (node (ref "IC5") (pin "8") (pinfunction "GND_8") (pintype "bidirectional"))
      (node (ref "IC6") (pin "8") (pinfunction "GND_8") (pintype "bidirectional"))
      (node (ref "IC7") (pin "8") (pinfunction "GND_8") (pintype "bidirectional"))
      (node (ref "IC8") (pin "8") (pinfunction "GND_8") (pintype "bidirectional"))
      (node (ref "IC9") (pin "4") (pinfunction "GND_4") (pintype "power_in"))
      (node (ref "J2") (pin "1") (pinfunction "1_1") (pintype "passive"))
      (node (ref "J3") (pin "3") (pinfunction "3_3") (pintype "passive"))
      (node (ref "J3") (pin "6") (pinfunction "6_6") (pintype "passive"))
      (node (ref "M1") (pin "03") (pinfunction "3/GND1_03") (pintype "passive"))
      (node (ref "M1") (pin "05") (pinfunction "5/GND2_05") (pintype "passive"))
      (node (ref "M1") (pin "07") (pinfunction "7_07") (pintype "passive"))
      (node (ref "M1") (pin "09") (pinfunction "9/GND3_09") (pintype "passive"))
      (node (ref "MT1") (pin "0") (pinfunction "GND_0") (pintype "passive"))
      (node (ref "MT1") (pin "1") (pinfunction "GND_1") (pintype "passive"))
      (node (ref "MT1") (pin "2") (pinfunction "GND_2") (pintype "passive"))
      (node (ref "MT1") (pin "3") (pinfunction "GND_3") (pintype "passive"))
      (node (ref "MT1") (pin "4") (pinfunction "GND_4") (pintype "passive"))
      (node (ref "MT1") (pin "5") (pinfunction "GND_5") (pintype "passive"))
      (node (ref "MT1") (pin "6") (pinfunction "GND_6") (pintype "passive"))
      (node (ref "MT1") (pin "7") (pinfunction "GND_7") (pintype "passive"))
      (node (ref "MT1") (pin "8") (pinfunction "GND_8") (pintype "passive"))
      (node (ref "MT2") (pin "0") (pinfunction "GND_0") (pintype "passive"))
      (node (ref "MT2") (pin "1") (pinfunction "GND_1") (pintype "passive"))
      (node (ref "MT2") (pin "2") (pinfunction "GND_2") (pintype "passive"))
      (node (ref "MT2") (pin "3") (pinfunction "GND_3") (pintype "passive"))
      (node (ref "MT2") (pin "4") (pinfunction "GND_4") (pintype "passive"))
      (node (ref "MT2") (pin "5") (pinfunction "GND_5") (pintype "passive"))
      (node (ref "MT2") (pin "6") (pinfunction "GND_6") (pintype "passive"))
      (node (ref "MT2") (pin "7") (pinfunction "GND_7") (pintype "passive"))
      (node (ref "MT2") (pin "8") (pinfunction "GND_8") (pintype "passive"))
      (node (ref "MT3") (pin "0") (pinfunction "GND_0") (pintype "passive"))
      (node (ref "MT3") (pin "1") (pinfunction "GND_1") (pintype "passive"))
      (node (ref "MT3") (pin "2") (pinfunction "GND_2") (pintype "passive"))
      (node (ref "MT3") (pin "3") (pinfunction "GND_3") (pintype "passive"))
      (node (ref "MT3") (pin "4") (pinfunction "GND_4") (pintype "passive"))
      (node (ref "MT3") (pin "5") (pinfunction "GND_5") (pintype "passive"))
      (node (ref "MT3") (pin "6") (pinfunction "GND_6") (pintype "passive"))
      (node (ref "MT3") (pin "7") (pinfunction "GND_7") (pintype "passive"))
      (node (ref "MT3") (pin "8") (pinfunction "GND_8") (pintype "passive"))
      (node (ref "MT4") (pin "0") (pinfunction "GND_0") (pintype "passive"))
      (node (ref "MT4") (pin "1") (pinfunction "GND_1") (pintype "passive"))
      (node (ref "MT4") (pin "2") (pinfunction "GND_2") (pintype "passive"))
      (node (ref "MT4") (pin "3") (pinfunction "GND_3") (pintype "passive"))
      (node (ref "MT4") (pin "4") (pinfunction "GND_4") (pintype "passive"))
      (node (ref "MT4") (pin "5") (pinfunction "GND_5") (pintype "passive"))
      (node (ref "MT4") (pin "6") (pinfunction "GND_6") (pintype "passive"))
      (node (ref "MT4") (pin "7") (pinfunction "GND_7") (pintype "passive"))
      (node (ref "MT4") (pin "8") (pinfunction "GND_8") (pintype "passive"))
      (node (ref "PS1") (pin "1") (pinfunction "CATHODE_1") (pintype "passive"))
      (node (ref "Q8") (pin "2") (pinfunction "E_2") (pintype "passive"))
      (node (ref "R17") (pin "2") (pinfunction "2_2") (pintype "passive"))
      (node (ref "R19") (pin "1") (pinfunction "1_1") (pintype "passive"))
      (node (ref "R2") (pin "1") (pinfunction "1_1") (pintype "passive"))
      (node (ref "R20") (pin "1") (pinfunction "1_1") (pintype "passive"))
      (node (ref "R7") (pin "1") (pinfunction "1_1") (pintype "passive"))
    )
    (net (code "5") (name "HV") (class "Default")
      (node (ref "C14") (pin "1") (pinfunction "1_1") (pintype "passive"))
      (node (ref "D2") (pin "1") (pinfunction "1_1") (pintype "passive"))
      (node (ref "R10") (pin "2") (pinfunction "2_2") (pintype "passive"))
      (node (ref "R11") (pin "2") (pinfunction "2_2") (pintype "passive"))
      (node (ref "R12") (pin "2") (pinfunction "2_2") (pintype "passive"))
      (node (ref "R13") (pin "2") (pinfunction "2_2") (pintype "passive"))
      (node (ref "R5") (pin "2") (pinfunction "2_2") (pintype "passive"))
      (node (ref "R6") (pin "2") (pinfunction "2_2") (pintype "passive"))
    )
    (net (code "6") (name "JTAG_TCK") (class "Default")
      (node (ref "IC14") (pin "52") (pinfunction "PC0_TCK_SWCLK_52") (pintype "bidirectional"))
      (node (ref "M1") (pin "04") (pinfunction "4/TCK_04") (pintype "passive"))
      (node (ref "R4") (pin "1") (pinfunction "1_1") (pintype "passive"))
    )
    (net (code "7") (name "JTAG_TDI") (class "Default")
      (node (ref "IC14") (pin "50") (pinfunction "PC2_TDI_50") (pintype "bidirectional"))
      (node (ref "M1") (pin "08") (pinfunction "8/TDI_08") (pintype "passive"))
    )
    (net (code "8") (name "JTAG_TDO") (class "Default")
      (node (ref "IC14") (pin "49") (pinfunction "PC3_TDO_SWO_49") (pintype "bidirectional"))
      (node (ref "M1") (pin "06") (pinfunction "6/TDO_06") (pintype "passive"))
    )
    (net (code "9") (name "JTAG_TMS") (class "Default")
      (node (ref "IC14") (pin "51") (pinfunction "PC1_TMS_SWDIO_51") (pintype "bidirectional"))
      (node (ref "M1") (pin "02") (pinfunction "2/TMS_02") (pintype "passive"))
      (node (ref "R3") (pin "1") (pinfunction "1_1") (pintype "passive"))
    )
    (net (code "10") (name "LED_SDI") (class "Default")
      (node (ref "IC14") (pin "64") (pinfunction "PD3_64") (pintype "bidirectional"))
      (node (ref "IC9") (pin "6") (pinfunction "SDI_6") (pintype "bidirectional"))
    )
    (net (code "11") (name "MCU_PWM") (class "Default")
      (node (ref "IC14") (pin "1") (pinfunction "PB6_1") (pintype "bidirectional"))
      (node (ref "IC5") (pin "13") (pinfunction "~{OE}_13") (pintype "input"))
      (node (ref "IC6") (pin "13") (pinfunction "~{OE}_13") (pintype "input"))
      (node (ref "IC7") (pin "13") (pinfunction "~{OE}_13") (pintype "input"))
      (node (ref "IC8") (pin "13") (pinfunction "~{OE}_13") (pintype "input"))
      (node (ref "R26") (pin "1") (pinfunction "1_1") (pintype "passive"))
    )
    (net (code "12") (name "Net-(D3-Pad2)") (class "Default")
      (node (ref "D3") (pin "2") (pinfunction "2_2") (pintype "passive"))
      (node (ref "J1") (pin "1") (pinfunction "1_1") (pintype "passive"))
    )
    (net (code "13") (name "Net-(IC1-1B)") (class "Default")
      (node (ref "IC1") (pin "1") (pinfunction "1B_1") (pintype "input"))
      (node (ref "IC5") (pin "6") (pinfunction "QG_6") (pintype "output"))
    )
    (net (code "14") (name "Net-(IC1-1C)") (class "Default")
      (node (ref "IC1") (pin "16") (pinfunction "1C_16") (pintype "bidirectional"))
      (node (ref "Q2") (pin "4") (pinfunction "K4_4") (pintype "bidirectional"))
    )
    (net (code "15") (name "Net-(IC1-2B)") (class "Default")
      (node (ref "IC1") (pin "2") (pinfunction "2B_2") (pintype "input"))
      (node (ref "IC5") (pin "5") (pinfunction "QF_5") (pintype "output"))
    )
    (net (code "16") (name "Net-(IC1-2C)") (class "Default")
      (node (ref "IC1") (pin "15") (pinfunction "2C_15") (pintype "bidirectional"))
      (node (ref "Q2") (pin "3") (pinfunction "K3_3") (pintype "bidirectional"))
    )
    (net (code "17") (name "Net-(IC1-3B)") (class "Default")
      (node (ref "IC1") (pin "3") (pinfunction "3B_3") (pintype "input"))
      (node (ref "IC5") (pin "4") (pinfunction "QE_4") (pintype "output"))
    )
    (net (code "18") (name "Net-(IC1-3C)") (class "Default")
      (node (ref "IC1") (pin "14") (pinfunction "3C_14") (pintype "bidirectional"))
      (node (ref "Q2") (pin "2") (pinfunction "K2_2") (pintype "bidirectional"))
    )
    (net (code "19") (name "Net-(IC1-4B)") (class "Default")
      (node (ref "IC1") (pin "4") (pinfunction "4B_4") (pintype "input"))
      (node (ref "IC5") (pin "3") (pinfunction "QD_3") (pintype "output"))
    )
    (net (code "20") (name "Net-(IC1-4C)") (class "Default")
      (node (ref "IC1") (pin "13") (pinfunction "4C_13") (pintype "bidirectional"))
      (node (ref "Q2") (pin "1") (pinfunction "K1_1") (pintype "bidirectional"))
    )
    (net (code "21") (name "Net-(IC1-5B)") (class "Default")
      (node (ref "IC1") (pin "5") (pinfunction "5B_5") (pintype "input"))
      (node (ref "IC5") (pin "2") (pinfunction "QC_2") (pintype "output"))
    )
    (net (code "22") (name "Net-(IC1-5C)") (class "Default")
      (node (ref "IC1") (pin "12") (pinfunction "5C_12") (pintype "bidirectional"))
      (node (ref "Q1") (pin "11") (pinfunction "K0_11") (pintype "bidirectional"))
    )
    (net (code "23") (name "Net-(IC1-6B)") (class "Default")
      (node (ref "IC1") (pin "6") (pinfunction "6B_6") (pintype "input"))
      (node (ref "IC5") (pin "1") (pinfunction "QB_1") (pintype "output"))
    )
    (net (code "24") (name "Net-(IC1-6C)") (class "Default")
      (node (ref "IC1") (pin "11") (pinfunction "6C_11") (pintype "bidirectional"))
      (node (ref "Q1") (pin "2") (pinfunction "K2_2") (pintype "bidirectional"))
    )
    (net (code "25") (name "Net-(IC1-7B)") (class "Default")
      (node (ref "IC1") (pin "7") (pinfunction "7B_7") (pintype "input"))
      (node (ref "IC5") (pin "15") (pinfunction "QA_15") (pintype "output"))
    )
    (net (code "26") (name "Net-(IC1-7C)") (class "Default")
      (node (ref "IC1") (pin "10") (pinfunction "7C_10") (pintype "bidirectional"))
      (node (ref "Q1") (pin "1") (pinfunction "K1_1") (pintype "bidirectional"))
    )
    (net (code "27") (name "Net-(IC2-1B)") (class "Default")
      (node (ref "IC2") (pin "1") (pinfunction "1B_1") (pintype "input"))
      (node (ref "IC6") (pin "6") (pinfunction "QG_6") (pintype "output"))
    )
    (net (code "28") (name "Net-(IC2-1C)") (class "Default")
      (node (ref "IC2") (pin "16") (pinfunction "1C_16") (pintype "bidirectional"))
      (node (ref "Q3") (pin "11") (pinfunction "K0_11") (pintype "bidirectional"))
    )
    (net (code "29") (name "Net-(IC2-2B)") (class "Default")
      (node (ref "IC2") (pin "2") (pinfunction "2B_2") (pintype "input"))
      (node (ref "IC6") (pin "5") (pinfunction "QF_5") (pintype "output"))
    )
    (net (code "30") (name "Net-(IC2-2C)") (class "Default")
      (node (ref "IC2") (pin "15") (pinfunction "2C_15") (pintype "bidirectional"))
      (node (ref "Q2") (pin "11") (pinfunction "K0_11") (pintype "bidirectional"))
    )
    (net (code "31") (name "Net-(IC2-3B)") (class "Default")
      (node (ref "IC2") (pin "3") (pinfunction "3B_3") (pintype "input"))
      (node (ref "IC6") (pin "4") (pinfunction "QE_4") (pintype "output"))
    )
    (net (code "32") (name "Net-(IC2-3C)") (class "Default")
      (node (ref "IC2") (pin "14") (pinfunction "3C_14") (pintype "bidirectional"))
      (node (ref "Q2") (pin "10") (pinfunction "K9_10") (pintype "bidirectional"))
    )
    (net (code "33") (name "Net-(IC2-4B)") (class "Default")
      (node (ref "IC2") (pin "4") (pinfunction "4B_4") (pintype "input"))
      (node (ref "IC6") (pin "3") (pinfunction "QD_3") (pintype "output"))
    )
    (net (code "34") (name "Net-(IC2-4C)") (class "Default")
      (node (ref "IC2") (pin "13") (pinfunction "4C_13") (pintype "bidirectional"))
      (node (ref "Q2") (pin "9") (pinfunction "K8_9") (pintype "bidirectional"))
    )
    (net (code "35") (name "Net-(IC2-5B)") (class "Default")
      (node (ref "IC2") (pin "5") (pinfunction "5B_5") (pintype "input"))
      (node (ref "IC6") (pin "2") (pinfunction "QC_2") (pintype "output"))
    )
    (net (code "36") (name "Net-(IC2-5C)") (class "Default")
      (node (ref "IC2") (pin "12") (pinfunction "5C_12") (pintype "bidirectional"))
      (node (ref "Q2") (pin "7") (pinfunction "K7_7") (pintype "bidirectional"))
    )
    (net (code "37") (name "Net-(IC2-6B)") (class "Default")
      (node (ref "IC2") (pin "6") (pinfunction "6B_6") (pintype "input"))
      (node (ref "IC6") (pin "1") (pinfunction "QB_1") (pintype "output"))
    )
    (net (code "38") (name "Net-(IC2-6C)") (class "Default")
      (node (ref "IC2") (pin "11") (pinfunction "6C_11") (pintype "bidirectional"))
      (node (ref "Q2") (pin "6") (pinfunction "K6_6") (pintype "bidirectional"))
    )
    (net (code "39") (name "Net-(IC2-7B)") (class "Default")
      (node (ref "IC2") (pin "7") (pinfunction "7B_7") (pintype "input"))
      (node (ref "IC6") (pin "15") (pinfunction "QA_15") (pintype "output"))
    )
    (net (code "40") (name "Net-(IC2-7C)") (class "Default")
      (node (ref "IC2") (pin "10") (pinfunction "7C_10") (pintype "bidirectional"))
      (node (ref "Q2") (pin "5") (pinfunction "K5_5") (pintype "bidirectional"))
    )
    (net (code "41") (name "Net-(IC3-1B)") (class "Default")
      (node (ref "IC3") (pin "1") (pinfunction "1B_1") (pintype "input"))
      (node (ref "IC7") (pin "6") (pinfunction "QG_6") (pintype "output"))
    )
    (net (code "42") (name "Net-(IC3-1C)") (class "Default")
      (node (ref "IC3") (pin "16") (pinfunction "1C_16") (pintype "bidirectional"))
      (node (ref "Q4") (pin "2") (pinfunction "K2_2") (pintype "bidirectional"))
    )
    (net (code "43") (name "Net-(IC3-2B)") (class "Default")
      (node (ref "IC3") (pin "2") (pinfunction "2B_2") (pintype "input"))
      (node (ref "IC7") (pin "5") (pinfunction "QF_5") (pintype "output"))
    )
    (net (code "44") (name "Net-(IC3-2C)") (class "Default")
      (node (ref "IC3") (pin "15") (pinfunction "2C_15") (pintype "bidirectional"))
      (node (ref "Q4") (pin "1") (pinfunction "K1_1") (pintype "bidirectional"))
    )
    (net (code "45") (name "Net-(IC3-3B)") (class "Default")
      (node (ref "IC3") (pin "3") (pinfunction "3B_3") (pintype "input"))
      (node (ref "IC7") (pin "4") (pinfunction "QE_4") (pintype "output"))
    )
    (net (code "46") (name "Net-(IC3-3C)") (class "Default")
      (node (ref "IC3") (pin "14") (pinfunction "3C_14") (pintype "bidirectional"))
      (node (ref "Q3") (pin "5") (pinfunction "K5_5") (pintype "bidirectional"))
    )
    (net (code "47") (name "Net-(IC3-4B)") (class "Default")
      (node (ref "IC3") (pin "4") (pinfunction "4B_4") (pintype "input"))
      (node (ref "IC7") (pin "3") (pinfunction "QD_3") (pintype "output"))
    )
    (net (code "48") (name "Net-(IC3-4C)") (class "Default")
      (node (ref "IC3") (pin "13") (pinfunction "4C_13") (pintype "bidirectional"))
      (node (ref "Q3") (pin "4") (pinfunction "K4_4") (pintype "bidirectional"))
    )
    (net (code "49") (name "Net-(IC3-5B)") (class "Default")
      (node (ref "IC3") (pin "5") (pinfunction "5B_5") (pintype "input"))
      (node (ref "IC7") (pin "2") (pinfunction "QC_2") (pintype "output"))
    )
    (net (code "50") (name "Net-(IC3-5C)") (class "Default")
      (node (ref "IC3") (pin "12") (pinfunction "5C_12") (pintype "bidirectional"))
      (node (ref "Q3") (pin "3") (pinfunction "K3_3") (pintype "bidirectional"))
    )
    (net (code "51") (name "Net-(IC3-6B)") (class "Default")
      (node (ref "IC3") (pin "6") (pinfunction "6B_6") (pintype "input"))
      (node (ref "IC7") (pin "1") (pinfunction "QB_1") (pintype "output"))
    )
    (net (code "52") (name "Net-(IC3-6C)") (class "Default")
      (node (ref "IC3") (pin "11") (pinfunction "6C_11") (pintype "bidirectional"))
      (node (ref "Q3") (pin "2") (pinfunction "K2_2") (pintype "bidirectional"))
    )
    (net (code "53") (name "Net-(IC3-7B)") (class "Default")
      (node (ref "IC3") (pin "7") (pinfunction "7B_7") (pintype "input"))
      (node (ref "IC7") (pin "15") (pinfunction "QA_15") (pintype "output"))
    )
    (net (code "54") (name "Net-(IC3-7C)") (class "Default")
      (node (ref "IC3") (pin "10") (pinfunction "7C_10") (pintype "bidirectional"))
      (node (ref "Q3") (pin "1") (pinfunction "K1_1") (pintype "bidirectional"))
    )
    (net (code "55") (name "Net-(IC4-1B)") (class "Default")
      (node (ref "IC4") (pin "1") (pinfunction "1B_1") (pintype "input"))
      (node (ref "IC8") (pin "6") (pinfunction "QG_6") (pintype "output"))
    )
    (net (code "56") (name "Net-(IC4-1C)") (class "Default")
      (node (ref "IC4") (pin "16") (pinfunction "1C_16") (pintype "bidirectional"))
      (node (ref "Q4") (pin "10") (pinfunction "K9_10") (pintype "bidirectional"))
    )
    (net (code "57") (name "Net-(IC4-2B)") (class "Default")
      (node (ref "IC4") (pin "2") (pinfunction "2B_2") (pintype "input"))
      (node (ref "IC8") (pin "5") (pinfunction "QF_5") (pintype "output"))
    )
    (net (code "58") (name "Net-(IC4-2C)") (class "Default")
      (node (ref "IC4") (pin "15") (pinfunction "2C_15") (pintype "bidirectional"))
      (node (ref "Q4") (pin "9") (pinfunction "K8_9") (pintype "bidirectional"))
    )
    (net (code "59") (name "Net-(IC4-3B)") (class "Default")
      (node (ref "IC4") (pin "3") (pinfunction "3B_3") (pintype "input"))
      (node (ref "IC8") (pin "4") (pinfunction "QE_4") (pintype "output"))
    )
    (net (code "60") (name "Net-(IC4-3C)") (class "Default")
      (node (ref "IC4") (pin "14") (pinfunction "3C_14") (pintype "bidirectional"))
      (node (ref "Q4") (pin "7") (pinfunction "K7_7") (pintype "bidirectional"))
    )
    (net (code "61") (name "Net-(IC4-4B)") (class "Default")
      (node (ref "IC4") (pin "4") (pinfunction "4B_4") (pintype "input"))
      (node (ref "IC8") (pin "3") (pinfunction "QD_3") (pintype "output"))
    )
    (net (code "62") (name "Net-(IC4-4C)") (class "Default")
      (node (ref "IC4") (pin "13") (pinfunction "4C_13") (pintype "bidirectional"))
      (node (ref "Q4") (pin "6") (pinfunction "K6_6") (pintype "bidirectional"))
    )
    (net (code "63") (name "Net-(IC4-5B)") (class "Default")
      (node (ref "IC4") (pin "5") (pinfunction "5B_5") (pintype "input"))
      (node (ref "IC8") (pin "2") (pinfunction "QC_2") (pintype "output"))
    )
    (net (code "64") (name "Net-(IC4-5C)") (class "Default")
      (node (ref "IC4") (pin "12") (pinfunction "5C_12") (pintype "bidirectional"))
      (node (ref "Q4") (pin "5") (pinfunction "K5_5") (pintype "bidirectional"))
    )
    (net (code "65") (name "Net-(IC4-6B)") (class "Default")
      (node (ref "IC4") (pin "6") (pinfunction "6B_6") (pintype "input"))
      (node (ref "IC8") (pin "1") (pinfunction "QB_1") (pintype "output"))
    )
    (net (code "66") (name "Net-(IC4-6C)") (class "Default")
      (node (ref "IC4") (pin "11") (pinfunction "6C_11") (pintype "bidirectional"))
      (node (ref "Q4") (pin "4") (pinfunction "K4_4") (pintype "bidirectional"))
    )
    (net (code "67") (name "Net-(IC4-7B)") (class "Default")
      (node (ref "IC4") (pin "7") (pinfunction "7B_7") (pintype "input"))
      (node (ref "IC8") (pin "15") (pinfunction "QA_15") (pintype "output"))
    )
    (net (code "68") (name "Net-(IC4-7C)") (class "Default")
      (node (ref "IC4") (pin "10") (pinfunction "7C_10") (pintype "bidirectional"))
      (node (ref "Q4") (pin "3") (pinfunction "K3_3") (pintype "bidirectional"))
    )
    (net (code "69") (name "Net-(IC5-QH')") (class "Default")
      (node (ref "IC5") (pin "9") (pinfunction "QH'_9") (pintype "output"))
      (node (ref "IC6") (pin "14") (pinfunction "SER_14") (pintype "input"))
    )
    (net (code "70") (name "Net-(IC6-QH')") (class "Default")
      (node (ref "IC6") (pin "9") (pinfunction "QH'_9") (pintype "output"))
      (node (ref "IC7") (pin "14") (pinfunction "SER_14") (pintype "input"))
    )
    (net (code "71") (name "Net-(IC7-QH')") (class "Default")
      (node (ref "IC7") (pin "9") (pinfunction "QH'_9") (pintype "output"))
      (node (ref "IC8") (pin "14") (pinfunction "SER_14") (pintype "input"))
    )
    (net (code "72") (name "Net-(IC8-QH)") (class "Default")
      (node (ref "IC8") (pin "7") (pinfunction "QH_7") (pintype "output"))
      (node (ref "R18") (pin "1") (pinfunction "1_1") (pintype "passive"))
    )
    (net (code "73") (name "Net-(IC9-IREF)") (class "Default")
      (node (ref "IC9") (pin "7") (pinfunction "IREF_7") (pintype "bidirectional"))
      (node (ref "R20") (pin "2") (pinfunction "2_2") (pintype "passive"))
    )
    (net (code "74") (name "Net-(IC9-OUT0)") (class "Default")
      (node (ref "IC9") (pin "1") (pinfunction "OUT0_1") (pintype "bidirectional"))
      (node (ref "LED1") (pin "3") (pinfunction "CRED_3") (pintype "passive"))
    )
    (net (code "75") (name "Net-(IC9-OUT1)") (class "Default")
      (node (ref "IC9") (pin "2") (pinfunction "OUT1_2") (pintype "bidirectional"))
      (node (ref "LED1") (pin "2") (pinfunction "CGREEN_2") (pintype "passive"))
    )
    (net (code "76") (name "Net-(IC9-OUT2)") (class "Default")
      (node (ref "IC9") (pin "3") (pinfunction "OUT2_3") (pintype "bidirectional"))
      (node (ref "LED1") (pin "1") (pinfunction "CBLUE_1") (pintype "passive"))
    )
    (net (code "77") (name "Net-(IC10-IREF)") (class "Default")
      (node (ref "IC10") (pin "7") (pinfunction "IREF_7") (pintype "bidirectional"))
      (node (ref "R19") (pin "2") (pinfunction "2_2") (pintype "passive"))
    )
    (net (code "78") (name "Net-(IC10-OUT0)") (class "Default")
      (node (ref "IC10") (pin "1") (pinfunction "OUT0_1") (pintype "bidirectional"))
      (node (ref "LED3") (pin "3") (pinfunction "CRED_3") (pintype "passive"))
    )
    (net (code "79") (name "Net-(IC10-OUT1)") (class "Default")
      (node (ref "IC10") (pin "2") (pinfunction "OUT1_2") (pintype "bidirectional"))
      (node (ref "LED3") (pin "2") (pinfunction "CGREEN_2") (pintype "passive"))
    )
    (net (code "80") (name "Net-(IC10-OUT2)") (class "Default")
      (node (ref "IC10") (pin "3") (pinfunction "OUT2_3") (pintype "bidirectional"))
      (node (ref "LED3") (pin "1") (pinfunction "CBLUE_1") (pintype "passive"))
    )
    (net (code "81") (name "Net-(IC10-SDI)") (class "Default")
      (node (ref "IC10") (pin "6") (pinfunction "SDI_6") (pintype "bidirectional"))
      (node (ref "IC9") (pin "5") (pinfunction "SDO_5") (pintype "bidirectional"))
    )
    (net (code "82") (name "Net-(IC13-CS)") (class "Default")
      (node (ref "IC13") (pin "8") (pinfunction "CS_8") (pintype "input"))
      (node (ref "Q7") (pin "3") (pinfunction "S_3") (pintype "passive"))
      (node (ref "R2") (pin "2") (pinfunction "2_2") (pintype "passive"))
    )
    (net (code "83") (name "Net-(IC13-EXT)") (class "Default")
      (node (ref "IC13") (pin "1") (pinfunction "EXT_1") (pintype "output"))
      (node (ref "Q7") (pin "1") (pinfunction "G_1") (pintype "passive"))
    )
    (net (code "84") (name "Net-(IC13-FB)") (class "Default")
      (node (ref "IC13") (pin "3") (pinfunction "FB_3") (pintype "input"))
      (node (ref "R16") (pin "P$1") (pinfunction "1_P$1") (pintype "passive"))
      (node (ref "R6") (pin "1") (pinfunction "1_1") (pintype "passive"))
    )
    (net (code "85") (name "Net-(IC13-REF)") (class "Default")
      (node (ref "C15") (pin "1") (pinfunction "1_1") (pintype "passive"))
      (node (ref "IC13") (pin "5") (pinfunction "REF_5") (pintype "bidirectional"))
    )
    (net (code "86") (name "Net-(IC14-OSC0)") (class "Default")
      (node (ref "C9") (pin "1") (pinfunction "1_1") (pintype "passive"))
      (node (ref "IC14") (pin "40") (pinfunction "OSC0_40") (pintype "input"))
      (node (ref "Y1") (pin "1") (pinfunction "1_1") (pintype "bidirectional"))
    )
    (net (code "87") (name "Net-(IC14-OSC1)") (class "Default")
      (node (ref "IC14") (pin "41") (pinfunction "OSC1_41") (pintype "output"))
      (node (ref "R21") (pin "2") (pinfunction "2_2") (pintype "passive"))
    )
    (net (code "88") (name "Net-(IC14-PE0)") (class "Default")
      (node (ref "IC14") (pin "9") (pinfunction "PE0_9") (pintype "bidirectional"))
      (node (ref "J3") (pin "1") (pinfunction "1_1") (pintype "passive"))
    )
    (net (code "89") (name "Net-(IC14-PE1)") (class "Default")
      (node (ref "C24") (pin "2") (pinfunction "2_2") (pintype "passive"))
      (node (ref "IC14") (pin "8") (pinfunction "PE1_8") (pintype "bidirectional"))
      (node (ref "R22") (pin "1") (pinfunction "1_1") (pintype "passive"))
    )
    (net (code "90") (name "Net-(IC14-PE2)") (class "Default")
      (node (ref "C25") (pin "2") (pinfunction "2_2") (pintype "passive"))
      (node (ref "IC14") (pin "7") (pinfunction "PE2_7") (pintype "bidirectional"))
      (node (ref "R23") (pin "1") (pinfunction "1_1") (pintype "passive"))
    )
    (net (code "91") (name "Net-(IC14-PE3)") (class "Default")
      (node (ref "IC14") (pin "6") (pinfunction "PE3_6") (pintype "bidirectional"))
      (node (ref "J3") (pin "5") (pinfunction "5_5") (pintype "passive"))
      (node (ref "R25") (pin "2") (pinfunction "2_2") (pintype "passive"))
    )
    (net (code "92") (name "Net-(IC14-VBAT)") (class "Default")
      (node (ref "C23") (pin "1") (pinfunction "1_1") (pintype "passive"))
      (node (ref "IC14") (pin "37") (pinfunction "VBAT_37") (pintype "power_in"))
      (node (ref "R8") (pin "2") (pinfunction "2_2") (pintype "passive"))
    )
    (net (code "93") (name "Net-(IC14-VDDC)") (class "Default")
      (node (ref "C6") (pin "1") (pinfunction "1_1") (pintype "passive"))
      (node (ref "IC14") (pin "25") (pinfunction "VDDC_2_25") (pintype "power_in"))
      (node (ref "IC14") (pin "56") (pinfunction "VDDC_56") (pintype "power_in"))
    )
    (net (code "94") (name "Net-(IC14-XOSC0)") (class "Default")
      (node (ref "C12") (pin "1") (pinfunction "1_1") (pintype "passive"))
      (node (ref "IC14") (pin "34") (pinfunction "XOSC0_34") (pintype "input"))
      (node (ref "Y2") (pin "2") (pinfunction "2_2") (pintype "bidirectional"))
    )
    (net (code "95") (name "Net-(IC14-XOSC1)") (class "Default")
      (node (ref "C11") (pin "1") (pinfunction "1_1") (pintype "passive"))
      (node (ref "IC14") (pin "36") (pinfunction "XOSC1_36") (pintype "output"))
      (node (ref "Y2") (pin "1") (pinfunction "1_1") (pintype "bidirectional"))
    )
    (net (code "96") (name "Net-(IC14-~{WAKE})") (class "Default")
      (node (ref "IC14") (pin "32") (pinfunction "~{WAKE}_32") (pintype "input"))
      (node (ref "R1") (pin "1") (pinfunction "1_1") (pintype "passive"))
    )
    (net (code "97") (name "Net-(J3-Pad2)") (class "Default")
      (node (ref "J3") (pin "2") (pinfunction "2_2") (pintype "passive"))
      (node (ref "R14") (pin "1") (pinfunction "1_1") (pintype "passive"))
      (node (ref "R23") (pin "2") (pinfunction "2_2") (pintype "passive"))
    )
    (net (code "98") (name "Net-(J3-Pad4)") (class "Default")
      (node (ref "J3") (pin "4") (pinfunction "4_4") (pintype "passive"))
      (node (ref "R22") (pin "2") (pinfunction "2_2") (pintype "passive"))
      (node (ref "R9") (pin "1") (pinfunction "1_1") (pintype "passive"))
    )
    (net (code "99") (name "Net-(LED1-ABLUE)") (class "Default")
      (node (ref "LED1") (pin "6") (pinfunction "ABLUE_6") (pintype "passive"))
      (node (ref "LED2") (pin "1") (pinfunction "CBLUE_1") (pintype "passive"))
    )
    (net (code "100") (name "Net-(LED1-AGREEN)") (class "Default")
      (node (ref "LED1") (pin "5") (pinfunction "AGREEN_5") (pintype "passive"))
      (node (ref "LED2") (pin "2") (pinfunction "CGREEN_2") (pintype "passive"))
    )
    (net (code "101") (name "Net-(LED1-ARED)") (class "Default")
      (node (ref "LED1") (pin "4") (pinfunction "ARED_4") (pintype "passive"))
      (node (ref "LED2") (pin "3") (pinfunction "CRED_3") (pintype "passive"))
    )
    (net (code "102") (name "Net-(LED3-ABLUE)") (class "Default")
      (node (ref "LED3") (pin "6") (pinfunction "ABLUE_6") (pintype "passive"))
      (node (ref "LED4") (pin "1") (pinfunction "CBLUE_1") (pintype "passive"))
    )
    (net (code "103") (name "Net-(LED3-AGREEN)") (class "Default")
      (node (ref "LED3") (pin "5") (pinfunction "AGREEN_5") (pintype "passive"))
      (node (ref "LED4") (pin "2") (pinfunction "CGREEN_2") (pintype "passive"))
    )
    (net (code "104") (name "Net-(LED3-ARED)") (class "Default")
      (node (ref "LED3") (pin "4") (pinfunction "ARED_4") (pintype "passive"))
      (node (ref "LED4") (pin "3") (pinfunction "CRED_3") (pintype "passive"))
    )
    (net (code "105") (name "Net-(Q1-A)") (class "Default")
      (node (ref "Q1") (pin "12") (pinfunction "A_12") (pintype "bidirectional"))
      (node (ref "R10") (pin "1") (pinfunction "1_1") (pintype "passive"))
    )
    (net (code "106") (name "Net-(Q2-A)") (class "Default")
      (node (ref "Q2") (pin "12") (pinfunction "A_12") (pintype "bidirectional"))
      (node (ref "R11") (pin "1") (pinfunction "1_1") (pintype "passive"))
    )
    (net (code "107") (name "Net-(Q3-A)") (class "Default")
      (node (ref "Q3") (pin "12") (pinfunction "A_12") (pintype "bidirectional"))
      (node (ref "R12") (pin "1") (pinfunction "1_1") (pintype "passive"))
    )
    (net (code "108") (name "Net-(Q4-A)") (class "Default")
      (node (ref "Q4") (pin "12") (pinfunction "A_12") (pintype "bidirectional"))
      (node (ref "R13") (pin "1") (pinfunction "1_1") (pintype "passive"))
    )
    (net (code "109") (name "Net-(Q4-K0)") (class "Default")
      (node (ref "D4") (pin "2") (pinfunction "2_2") (pintype "passive"))
      (node (ref "Q4") (pin "11") (pinfunction "K0_11") (pintype "bidirectional"))
      (node (ref "Q8") (pin "3") (pinfunction "C_3") (pintype "passive"))
    )
    (net (code "110") (name "Net-(Q7-D)") (class "Default")
      (node (ref "D2") (pin "2") (pinfunction "2_2") (pintype "passive"))
      (node (ref "L1") (pin "2") (pinfunction "2_2") (pintype "passive"))
      (node (ref "Q7") (pin "4") (pinfunction "D_4") (pintype "passive"))
    )
    (net (code "111") (name "Net-(Q8-B)") (class "Default")
      (node (ref "Q8") (pin "1") (pinfunction "B_1") (pintype "passive"))
      (node (ref "R17") (pin "1") (pinfunction "1_1") (pintype "passive"))
      (node (ref "R18") (pin "2") (pinfunction "2_2") (pintype "passive"))
    )
    (net (code "112") (name "Net-(R16-2)") (class "Default")
      (node (ref "R16") (pin "P$2") (pinfunction "2_P$2") (pintype "passive"))
      (node (ref "R16") (pin "P$3") (pinfunction "3_P$3") (pintype "passive"))
      (node (ref "R7") (pin "2") (pinfunction "2_2") (pintype "passive"))
    )
    (net (code "113") (name "Net-(R24-Pad2)") (class "Default")
      (node (ref "R24") (pin "2") (pinfunction "2_2") (pintype "passive"))
      (node (ref "R25") (pin "1") (pinfunction "1_1") (pintype "passive"))
    )
    (net (code "114") (name "Net-(Y1-2)") (class "Default")
      (node (ref "C10") (pin "1") (pinfunction "1_1") (pintype "passive"))
      (node (ref "R21") (pin "1") (pinfunction "1_1") (pintype "passive"))
      (node (ref "Y1") (pin "3") (pinfunction "2_3") (pintype "bidirectional"))
    )
    (net (code "115") (name "SR_RCLK") (class "Default")
      (node (ref "IC14") (pin "23") (pinfunction "PA6_23") (pintype "bidirectional"))
      (node (ref "IC5") (pin "12") (pinfunction "RCLK_12") (pintype "input"))
      (node (ref "IC6") (pin "12") (pinfunction "RCLK_12") (pintype "input"))
      (node (ref "IC7") (pin "12") (pinfunction "RCLK_12") (pintype "input"))
      (node (ref "IC8") (pin "12") (pinfunction "RCLK_12") (pintype "input"))
    )
    (net (code "116") (name "SR_SER") (class "Default")
      (node (ref "IC14") (pin "22") (pinfunction "PA5_SSI0TX_22") (pintype "bidirectional"))
      (node (ref "IC5") (pin "14") (pinfunction "SER_14") (pintype "input"))
    )
    (net (code "117") (name "SR_SRCLK") (class "Default")
      (node (ref "IC14") (pin "19") (pinfunction "PA2_SSI0CLK_19") (pintype "bidirectional"))
      (node (ref "IC5") (pin "11") (pinfunction "SRCLK_11") (pintype "input"))
      (node (ref "IC6") (pin "11") (pinfunction "SRCLK_11") (pintype "input"))
      (node (ref "IC7") (pin "11") (pinfunction "SRCLK_11") (pintype "input"))
      (node (ref "IC8") (pin "11") (pinfunction "SRCLK_11") (pintype "input"))
    )
    (net (code "118") (name "VBAT") (class "Default")
      (node (ref "PS1") (pin "2") (pinfunction "ANODE_2") (pintype "passive"))
      (node (ref "R8") (pin "1") (pinfunction "1_1") (pintype "passive"))
    )
    (net (code "119") (name "unconnected-(IC5-QH-Pad7)") (class "Default")
      (node (ref "IC5") (pin "7") (pinfunction "QH_7") (pintype "output"))
    )
    (net (code "120") (name "unconnected-(IC6-QH-Pad7)") (class "Default")
      (node (ref "IC6") (pin "7") (pinfunction "QH_7") (pintype "output"))
    )
    (net (code "121") (name "unconnected-(IC7-QH-Pad7)") (class "Default")
      (node (ref "IC7") (pin "7") (pinfunction "QH_7") (pintype "output"))
    )
    (net (code "122") (name "unconnected-(IC8-QH'-Pad9)") (class "Default")
      (node (ref "IC8") (pin "9") (pinfunction "QH'_9") (pintype "output"))
    )
    (net (code "123") (name "unconnected-(IC10-SDO-Pad5)") (class "Default")
      (node (ref "IC10") (pin "5") (pinfunction "SDO_5") (pintype "bidirectional"))
    )
    (net (code "124") (name "unconnected-(IC14-PA0_U0RX-Pad17)") (class "Default")
      (node (ref "IC14") (pin "17") (pinfunction "PA0_U0RX_17") (pintype "bidirectional"))
    )
    (net (code "125") (name "unconnected-(IC14-PA1_U0TX-Pad18)") (class "Default")
      (node (ref "IC14") (pin "18") (pinfunction "PA1_U0TX_18") (pintype "bidirectional"))
    )
    (net (code "126") (name "unconnected-(IC14-PA3_SSI0FSS-Pad20)") (class "Default")
      (node (ref "IC14") (pin "20") (pinfunction "PA3_SSI0FSS_20") (pintype "bidirectional"))
    )
    (net (code "127") (name "unconnected-(IC14-PA4_SSI0RX-Pad21)") (class "Default")
      (node (ref "IC14") (pin "21") (pinfunction "PA4_SSI0RX_21") (pintype "bidirectional"))
    )
    (net (code "128") (name "unconnected-(IC14-PA7-Pad24)") (class "Default")
      (node (ref "IC14") (pin "24") (pinfunction "PA7_24") (pintype "bidirectional"))
    )
    (net (code "129") (name "unconnected-(IC14-PB0-Pad45)") (class "Default")
      (node (ref "IC14") (pin "45") (pinfunction "PB0_45") (pintype "bidirectional"))
    )
    (net (code "130") (name "unconnected-(IC14-PB1-Pad46)") (class "Default")
      (node (ref "IC14") (pin "46") (pinfunction "PB1_46") (pintype "bidirectional"))
    )
    (net (code "131") (name "unconnected-(IC14-PB2_I2C0SCL-Pad47)") (class "Default")
      (node (ref "IC14") (pin "47") (pinfunction "PB2_I2C0SCL_47") (pintype "bidirectional"))
    )
    (net (code "132") (name "unconnected-(IC14-PB3_I2C0SDA-Pad48)") (class "Default")
      (node (ref "IC14") (pin "48") (pinfunction "PB3_I2C0SDA_48") (pintype "bidirectional"))
    )
    (net (code "133") (name "unconnected-(IC14-PB4-Pad58)") (class "Default")
      (node (ref "IC14") (pin "58") (pinfunction "PB4_58") (pintype "bidirectional"))
    )
    (net (code "134") (name "unconnected-(IC14-PB5-Pad57)") (class "Default")
      (node (ref "IC14") (pin "57") (pinfunction "PB5_57") (pintype "bidirectional"))
    )
    (net (code "135") (name "unconnected-(IC14-PB7-Pad4)") (class "Default")
      (node (ref "IC14") (pin "4") (pinfunction "PB7_4") (pintype "bidirectional"))
    )
    (net (code "136") (name "unconnected-(IC14-PC4-Pad16)") (class "Default")
      (node (ref "IC14") (pin "16") (pinfunction "PC4_16") (pintype "bidirectional"))
    )
    (net (code "137") (name "unconnected-(IC14-PC5-Pad15)") (class "Default")
      (node (ref "IC14") (pin "15") (pinfunction "PC5_15") (pintype "bidirectional"))
    )
    (net (code "138") (name "unconnected-(IC14-PC6-Pad14)") (class "Default")
      (node (ref "IC14") (pin "14") (pinfunction "PC6_14") (pintype "bidirectional"))
    )
    (net (code "139") (name "unconnected-(IC14-PC7-Pad13)") (class "Default")
      (node (ref "IC14") (pin "13") (pinfunction "PC7_13") (pintype "bidirectional"))
    )
    (net (code "140") (name "unconnected-(IC14-PD0-Pad61)") (class "Default")
      (node (ref "IC14") (pin "61") (pinfunction "PD0_61") (pintype "bidirectional"))
    )
    (net (code "141") (name "unconnected-(IC14-PD1-Pad62)") (class "Default")
      (node (ref "IC14") (pin "62") (pinfunction "PD1_62") (pintype "bidirectional"))
    )
    (net (code "142") (name "unconnected-(IC14-PD2-Pad63)") (class "Default")
      (node (ref "IC14") (pin "63") (pinfunction "PD2_63") (pintype "bidirectional"))
    )
    (net (code "143") (name "unconnected-(IC14-PD4-Pad43)") (class "Default")
      (node (ref "IC14") (pin "43") (pinfunction "PD4_43") (pintype "bidirectional"))
    )
    (net (code "144") (name "unconnected-(IC14-PD5-Pad44)") (class "Default")
      (node (ref "IC14") (pin "44") (pinfunction "PD5_44") (pintype "bidirectional"))
    )
    (net (code "145") (name "unconnected-(IC14-PD6-Pad53)") (class "Default")
      (node (ref "IC14") (pin "53") (pinfunction "PD6_53") (pintype "bidirectional"))
    )
    (net (code "146") (name "unconnected-(IC14-PD7-Pad10)") (class "Default")
      (node (ref "IC14") (pin "10") (pinfunction "PD7_10") (pintype "bidirectional"))
    )
    (net (code "147") (name "unconnected-(IC14-PE4-Pad59)") (class "Default")
      (node (ref "IC14") (pin "59") (pinfunction "PE4_59") (pintype "bidirectional"))
    )
    (net (code "148") (name "unconnected-(IC14-PE5-Pad60)") (class "Default")
      (node (ref "IC14") (pin "60") (pinfunction "PE5_60") (pintype "bidirectional"))
    )
    (net (code "149") (name "unconnected-(IC14-PF0-Pad28)") (class "Default")
      (node (ref "IC14") (pin "28") (pinfunction "PF0_28") (pintype "bidirectional"))
    )
    (net (code "150") (name "unconnected-(IC14-PF1-Pad29)") (class "Default")
      (node (ref "IC14") (pin "29") (pinfunction "PF1_29") (pintype "bidirectional"))
    )
    (net (code "151") (name "unconnected-(IC14-PF2-Pad30)") (class "Default")
      (node (ref "IC14") (pin "30") (pinfunction "PF2_30") (pintype "bidirectional"))
    )
    (net (code "152") (name "unconnected-(IC14-PF3-Pad31)") (class "Default")
      (node (ref "IC14") (pin "31") (pinfunction "PF3_31") (pintype "bidirectional"))
    )
    (net (code "153") (name "unconnected-(IC14-PF4-Pad5)") (class "Default")
      (node (ref "IC14") (pin "5") (pinfunction "PF4_5") (pintype "bidirectional"))
    )
    (net (code "154") (name "unconnected-(IC14-~{HIB}-Pad33)") (class "Default")
      (node (ref "IC14") (pin "33") (pinfunction "~{HIB}_33") (pintype "output"))
    )
    (net (code "155") (name "unconnected-(Q1-K3-Pad3)") (class "Default")
      (node (ref "Q1") (pin "3") (pinfunction "K3_3") (pintype "bidirectional"))
    )
    (net (code "156") (name "unconnected-(Q1-K4-Pad4)") (class "Default")
      (node (ref "Q1") (pin "4") (pinfunction "K4_4") (pintype "bidirectional"))
    )
    (net (code "157") (name "unconnected-(Q1-K5-Pad5)") (class "Default")
      (node (ref "Q1") (pin "5") (pinfunction "K5_5") (pintype "bidirectional"))
    )
    (net (code "158") (name "unconnected-(Q1-K6-Pad6)") (class "Default")
      (node (ref "Q1") (pin "6") (pinfunction "K6_6") (pintype "bidirectional"))
    )
    (net (code "159") (name "unconnected-(Q1-K7-Pad7)") (class "Default")
      (node (ref "Q1") (pin "7") (pinfunction "K7_7") (pintype "bidirectional"))
    )
    (net (code "160") (name "unconnected-(Q1-K8-Pad9)") (class "Default")
      (node (ref "Q1") (pin "9") (pinfunction "K8_9") (pintype "bidirectional"))
    )
    (net (code "161") (name "unconnected-(Q1-K9-Pad10)") (class "Default")
      (node (ref "Q1") (pin "10") (pinfunction "K9_10") (pintype "bidirectional"))
    )
    (net (code "162") (name "unconnected-(Q1-KD-Pad8)") (class "Default")
      (node (ref "Q1") (pin "8") (pinfunction "KD_8") (pintype "bidirectional"))
    )
    (net (code "163") (name "unconnected-(Q2-KD-Pad8)") (class "Default")
      (node (ref "Q2") (pin "8") (pinfunction "KD_8") (pintype "bidirectional"))
    )
    (net (code "164") (name "unconnected-(Q3-K6-Pad6)") (class "Default")
      (node (ref "Q3") (pin "6") (pinfunction "K6_6") (pintype "bidirectional"))
    )
    (net (code "165") (name "unconnected-(Q3-K7-Pad7)") (class "Default")
      (node (ref "Q3") (pin "7") (pinfunction "K7_7") (pintype "bidirectional"))
    )
    (net (code "166") (name "unconnected-(Q3-K8-Pad9)") (class "Default")
      (node (ref "Q3") (pin "9") (pinfunction "K8_9") (pintype "bidirectional"))
    )
    (net (code "167") (name "unconnected-(Q3-K9-Pad10)") (class "Default")
      (node (ref "Q3") (pin "10") (pinfunction "K9_10") (pintype "bidirectional"))
    )
    (net (code "168") (name "unconnected-(Q3-KD-Pad8)") (class "Default")
      (node (ref "Q3") (pin "8") (pinfunction "KD_8") (pintype "bidirectional"))
    )
    (net (code "169") (name "unconnected-(Q4-KD-Pad8)") (class "Default")
      (node (ref "Q4") (pin "8") (pinfunction "KD_8") (pintype "bidirectional"))
    )
    (net (code "170") (name "~{JTAG_RST}") (class "Default")
      (node (ref "IC11") (pin "5") (pinfunction "PWRGD_5") (pintype "bidirectional"))
      (node (ref "IC14") (pin "38") (pinfunction "~{RST}_38") (pintype "input"))
      (node (ref "M1") (pin "10") (pinfunction "~{10/RST}_10") (pintype "passive"))
      (node (ref "R15") (pin "1") (pinfunction "1_1") (pintype "passive"))
    )
  )
)
